# tNode-8.net
KiCad netlist of a schematic drawn in EAGLE
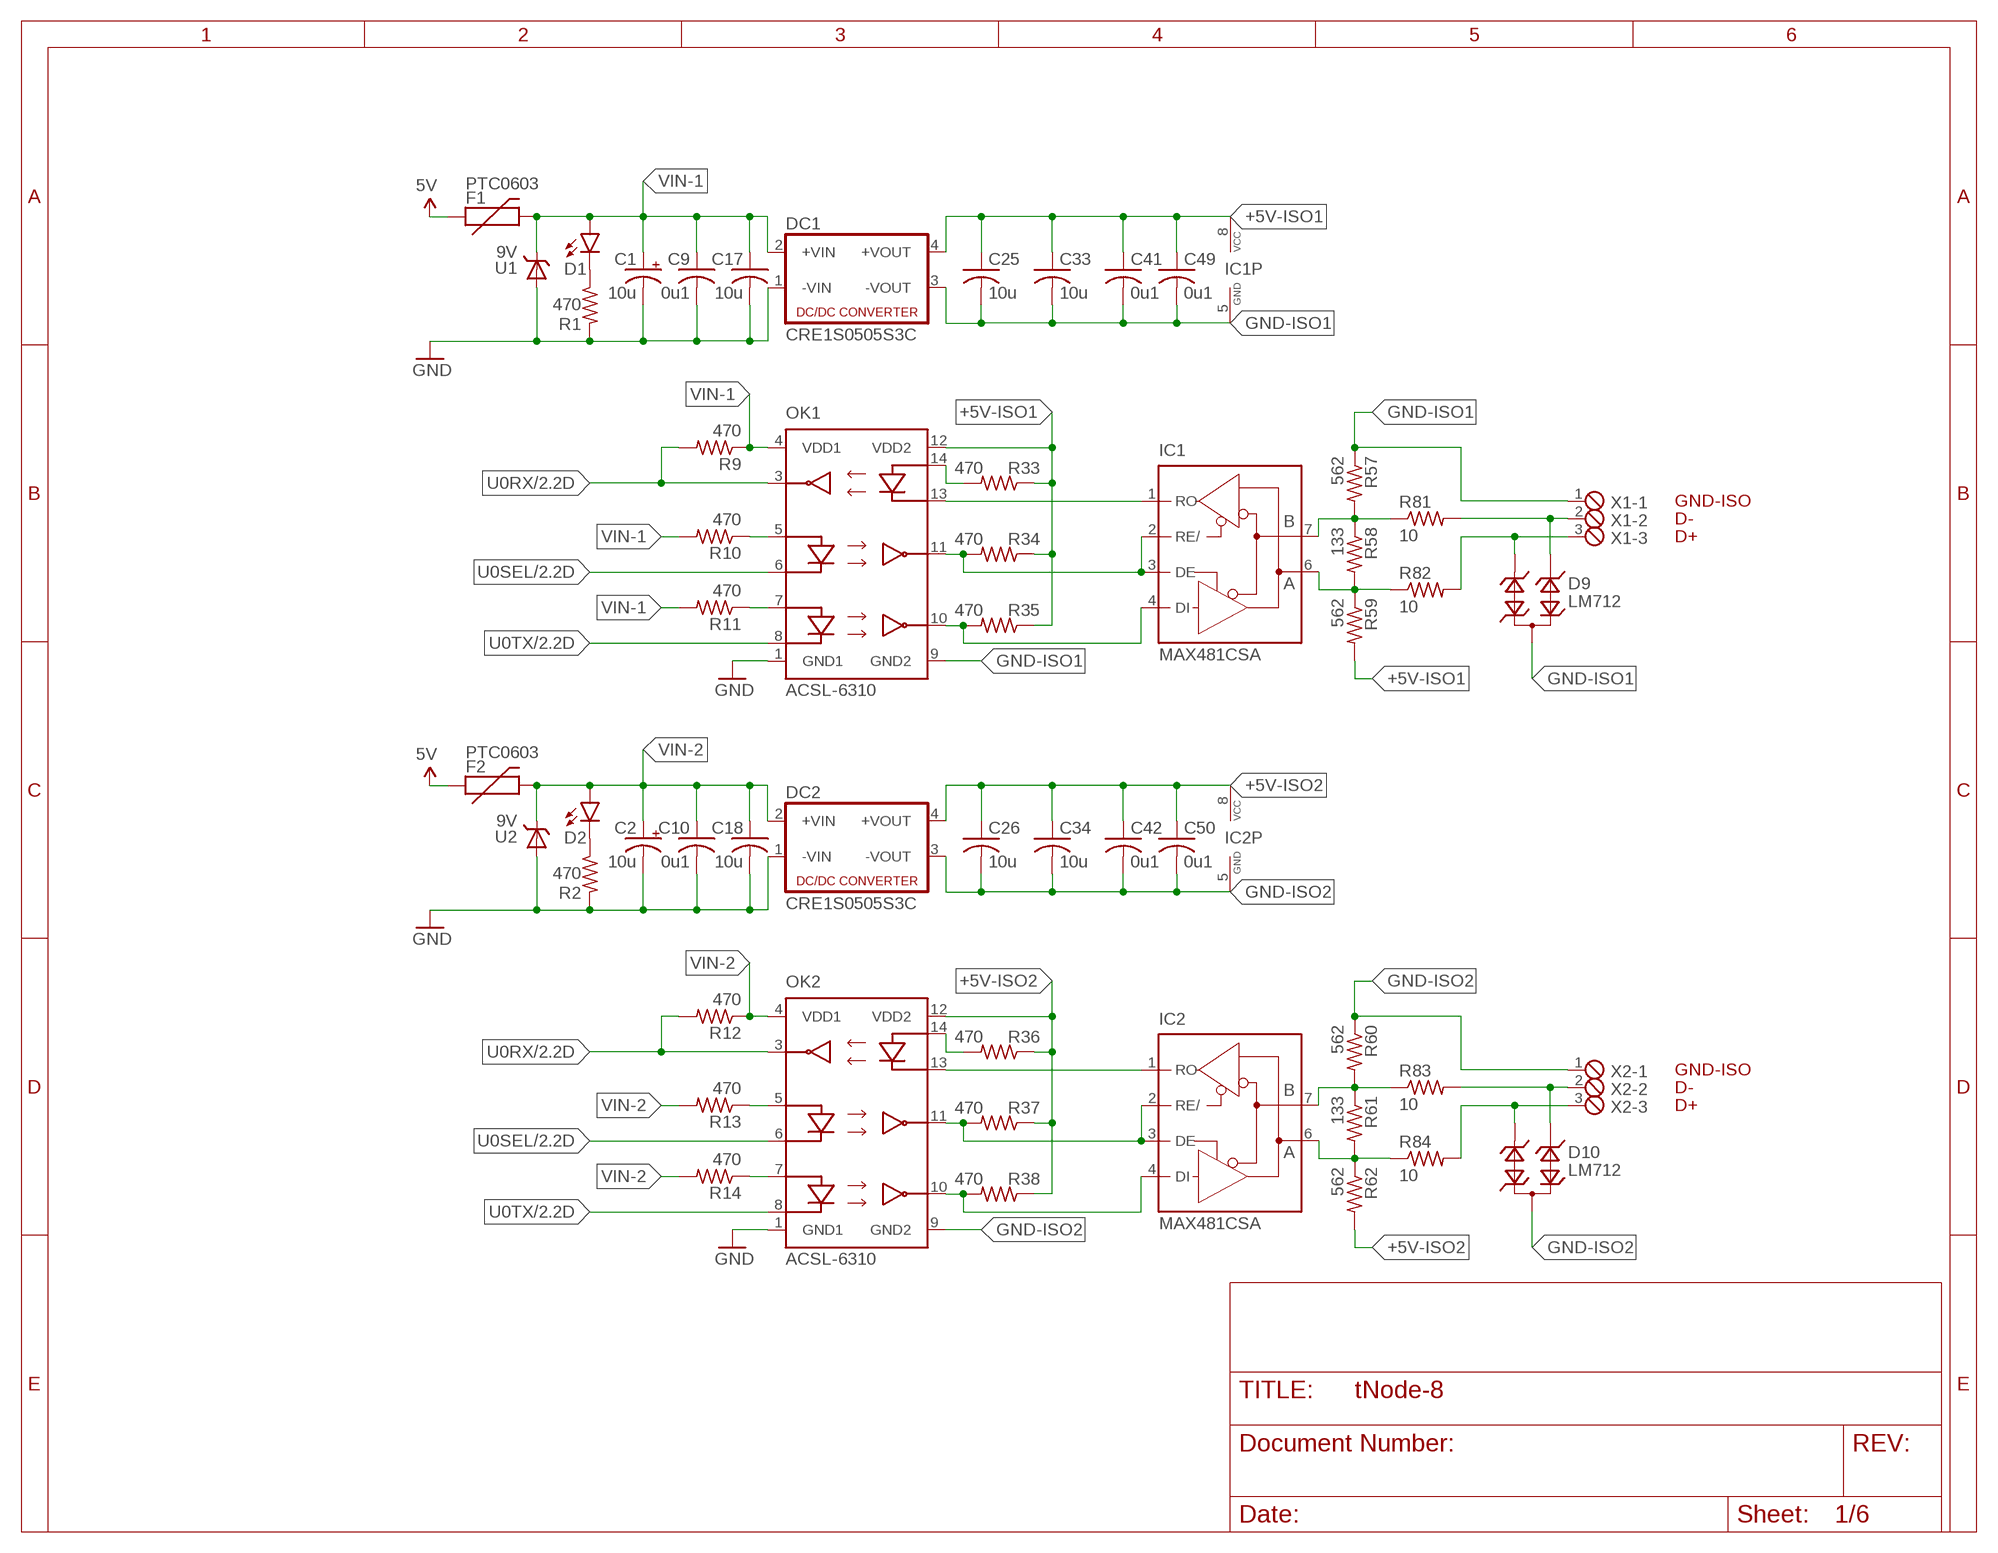
[diagram p0: schematic, sheet 1]
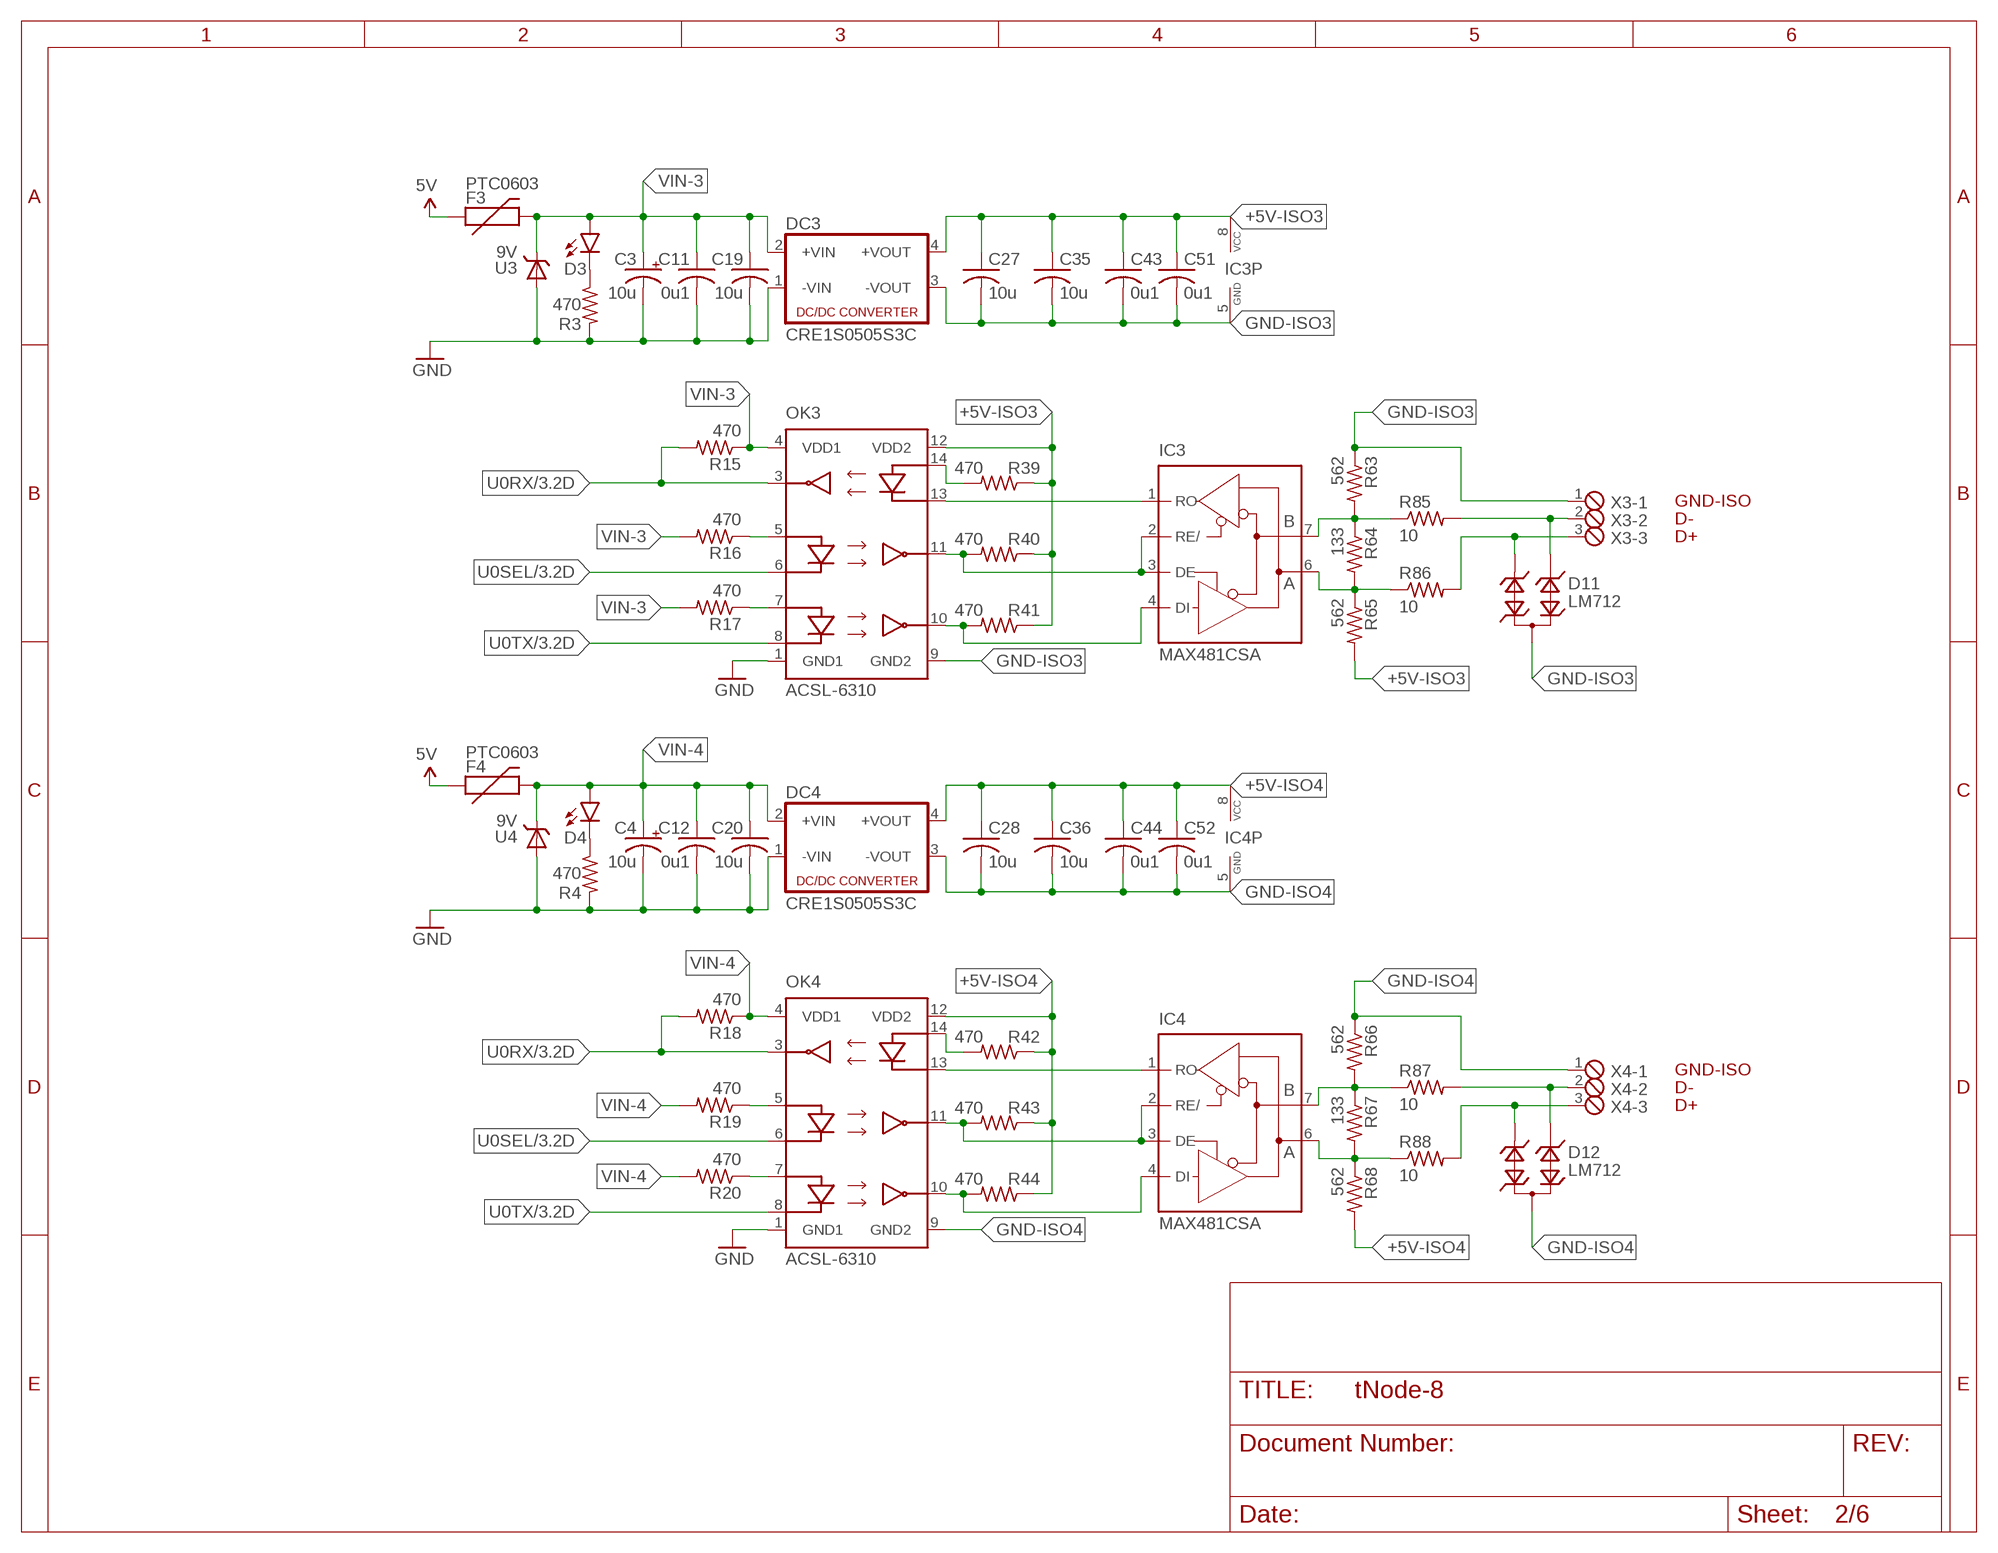
[diagram p1: schematic, sheet 2]
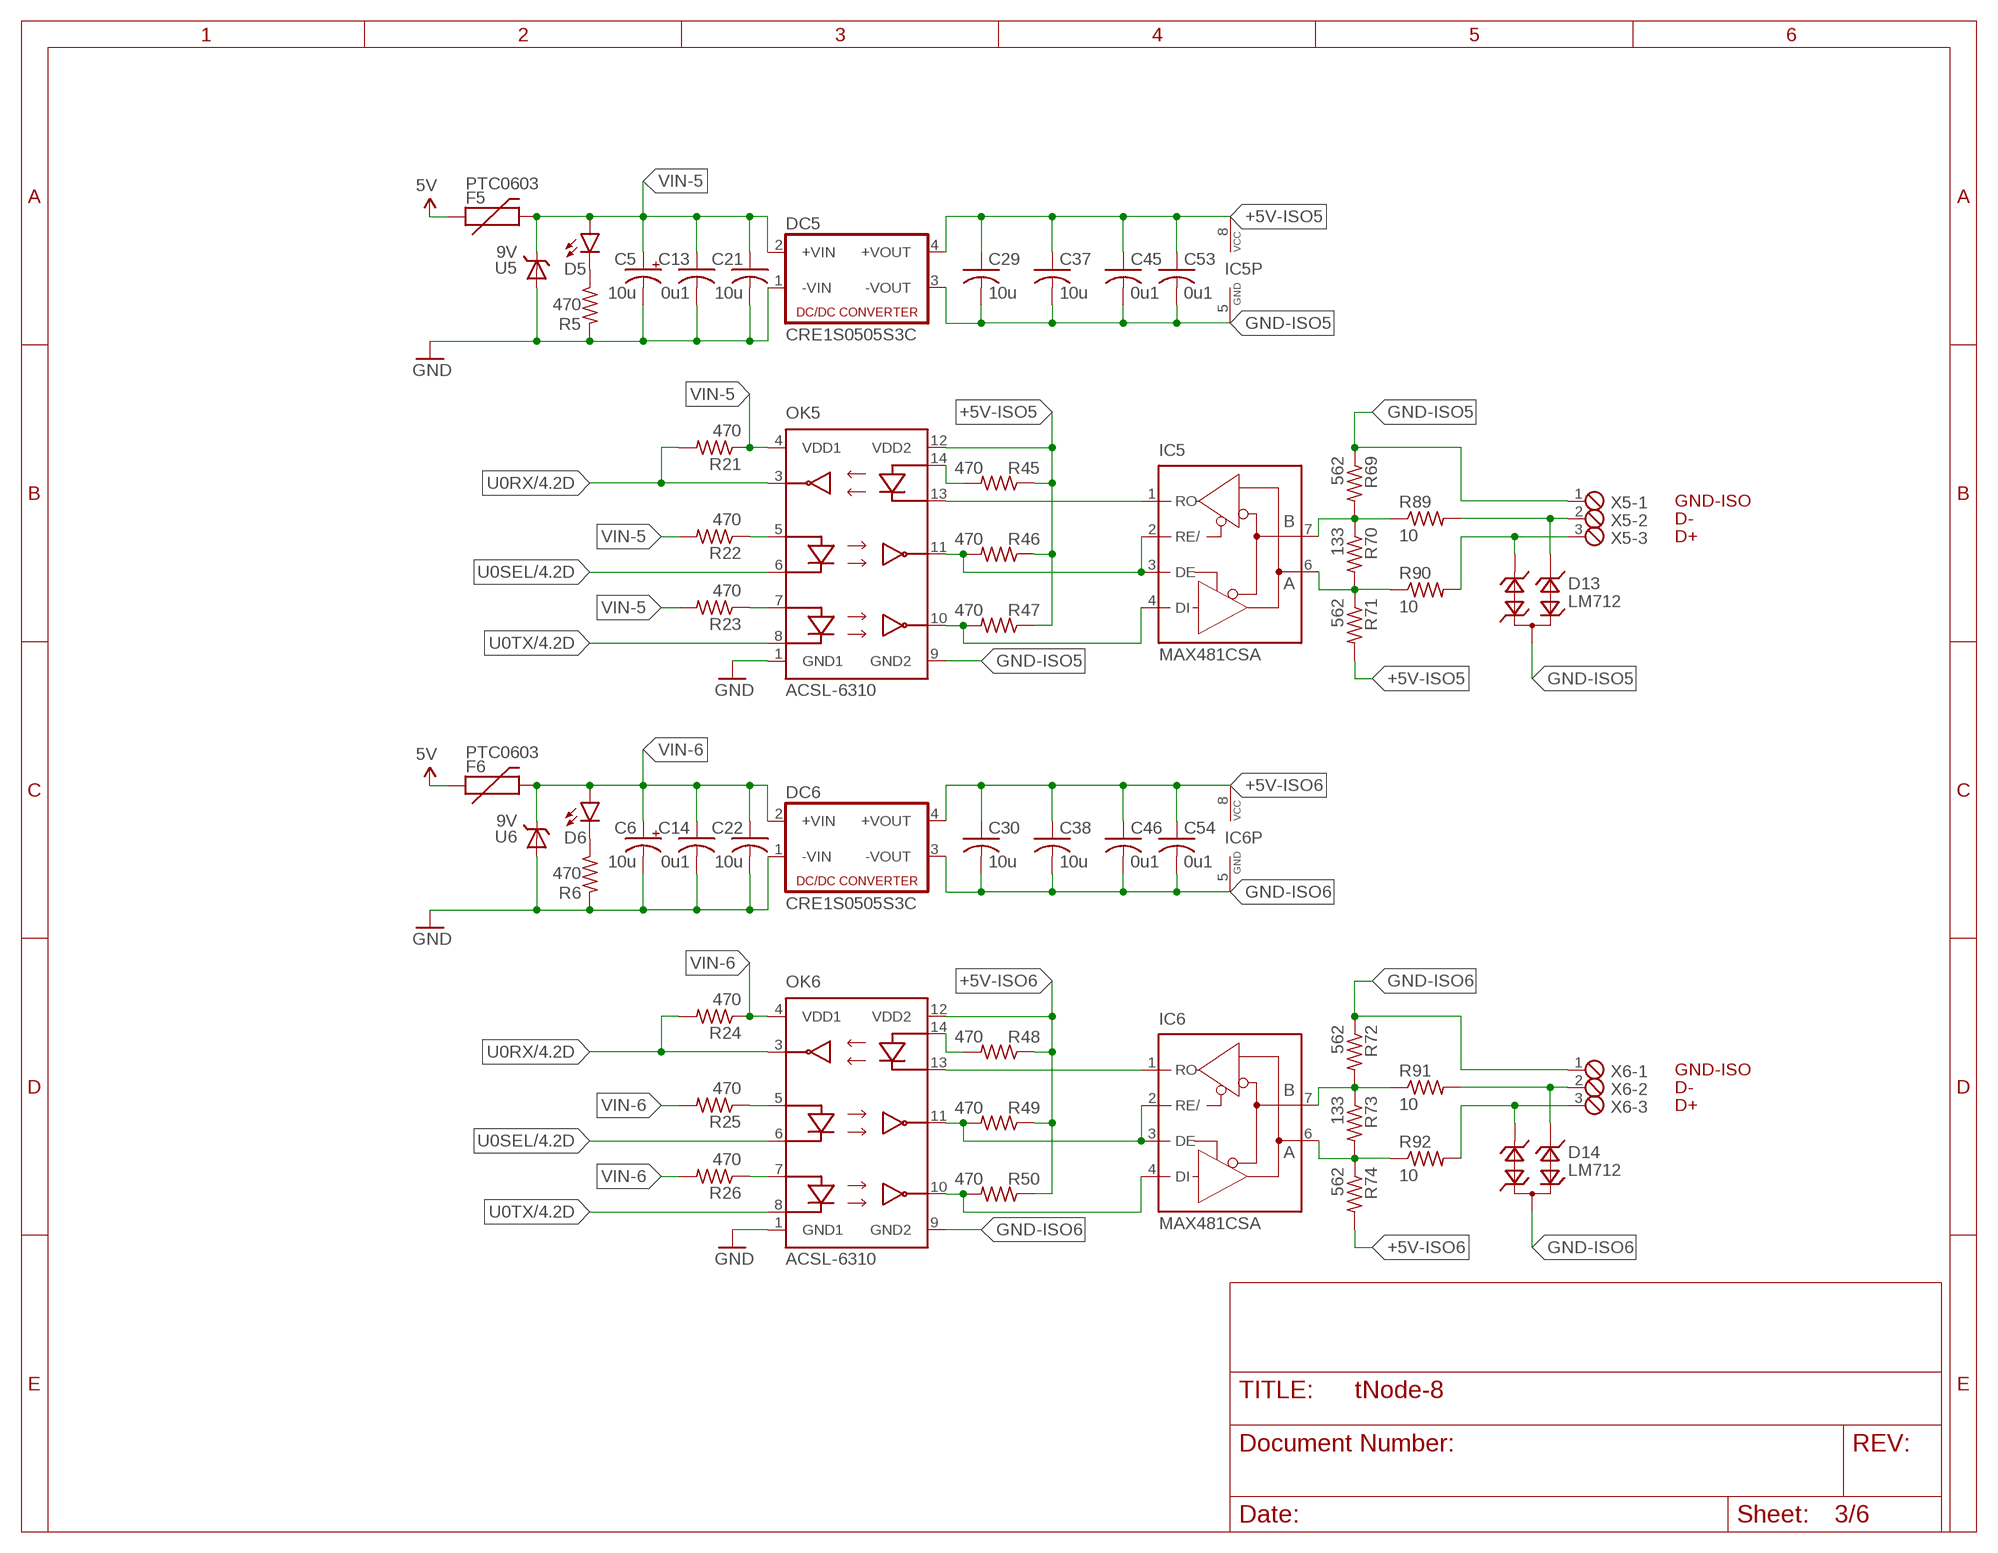
[diagram p2: schematic, sheet 3]
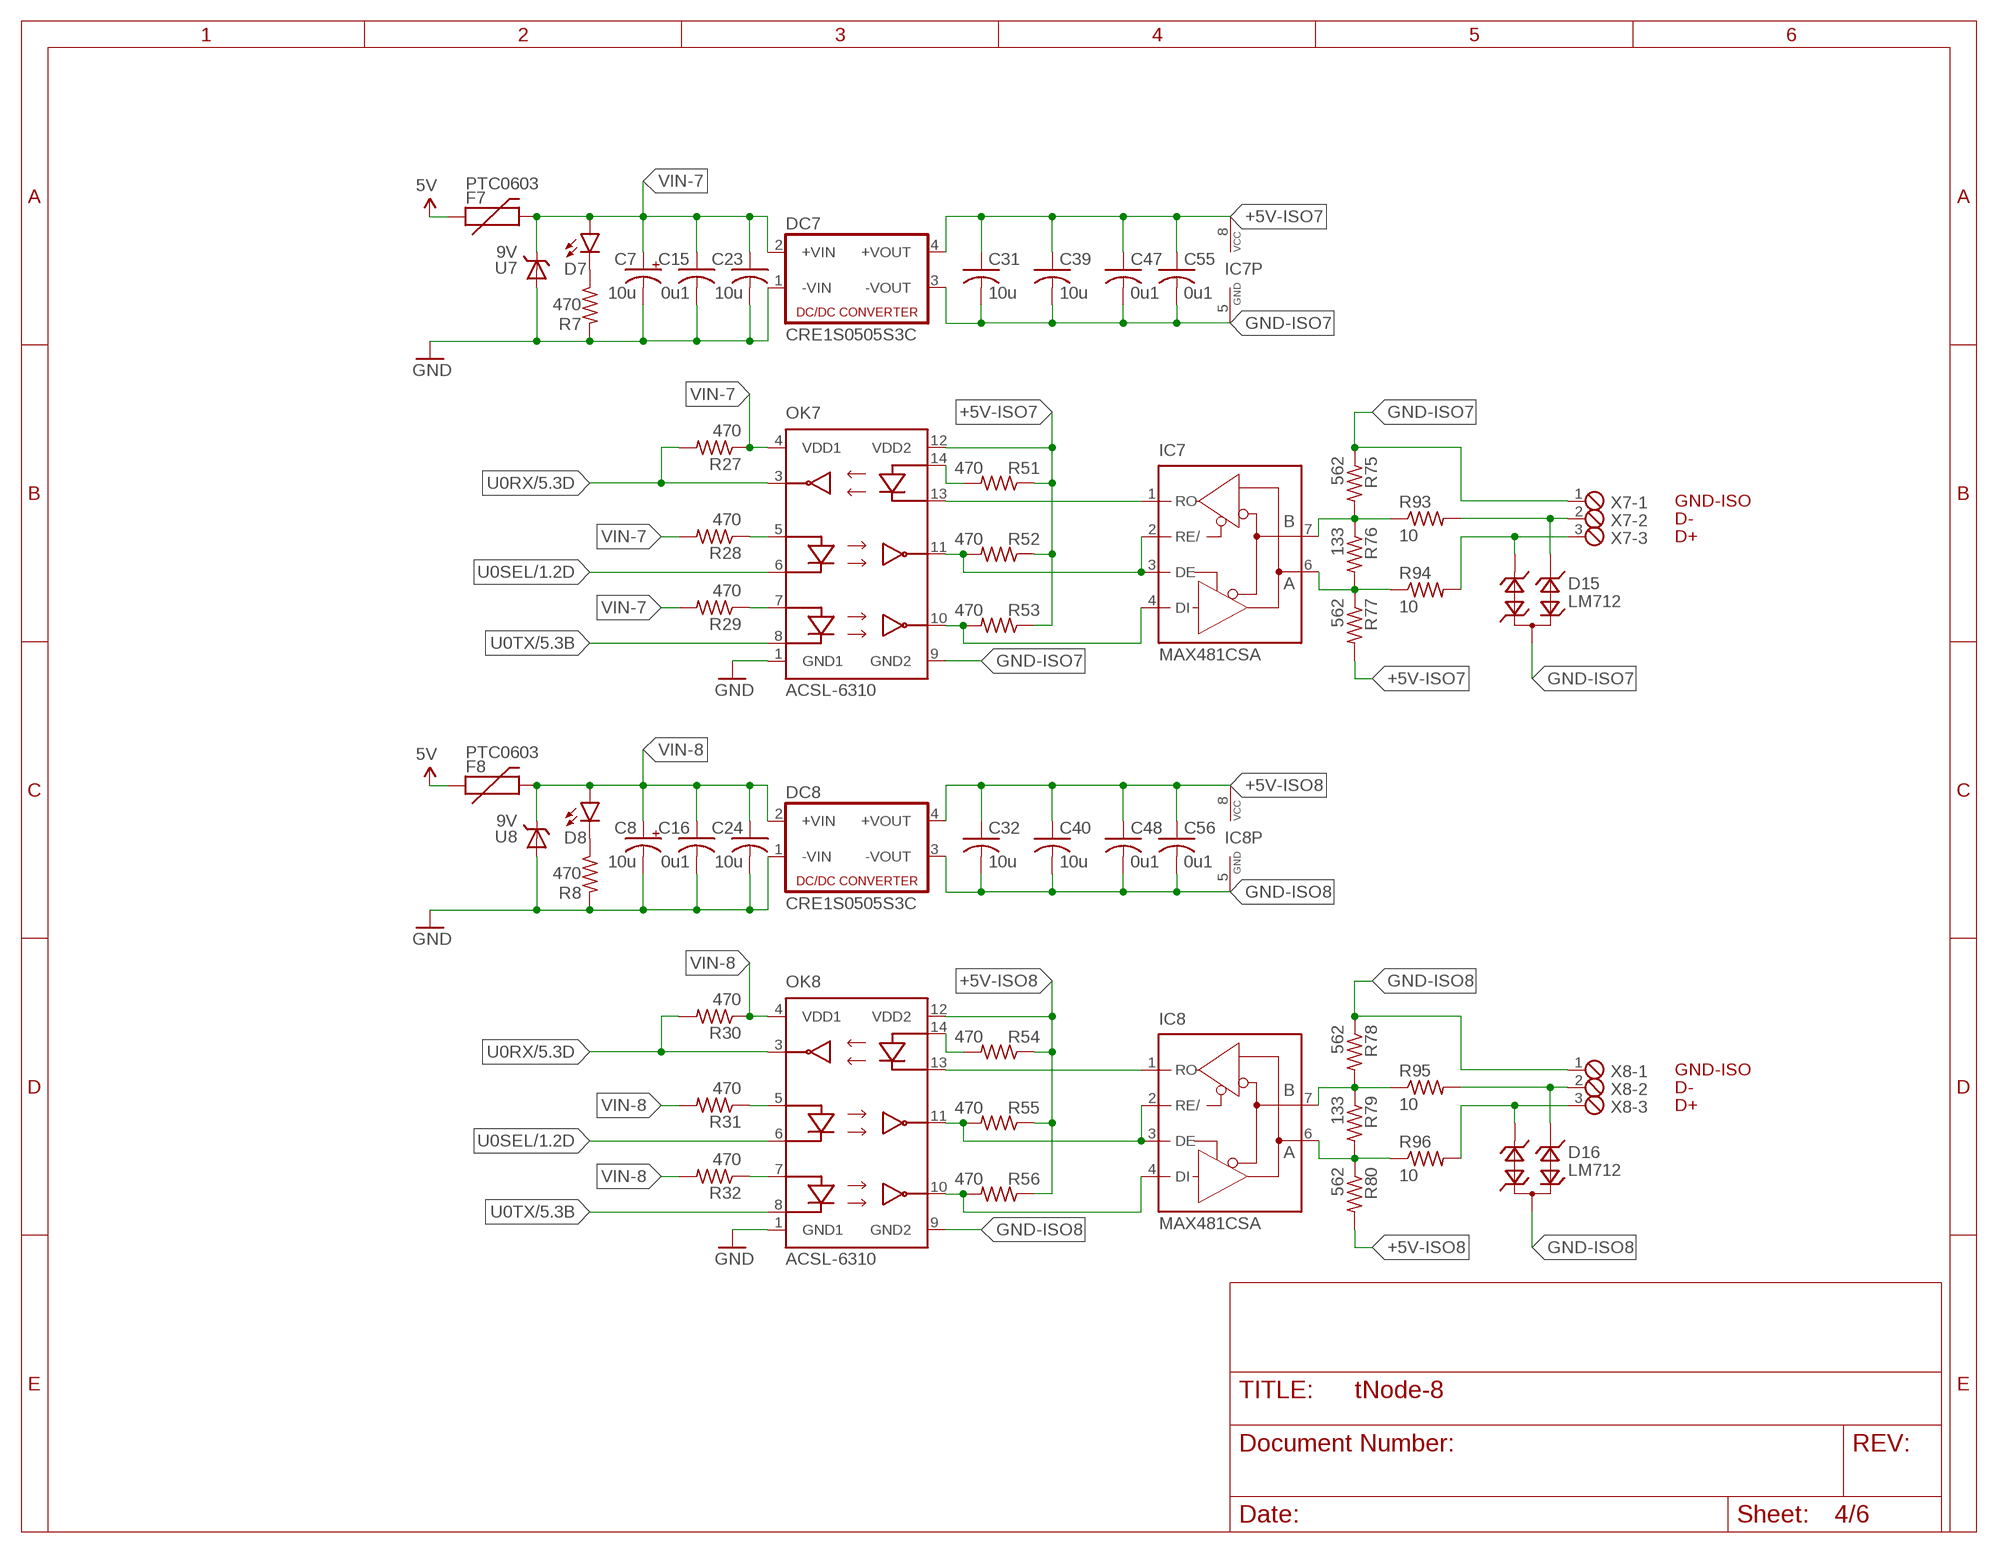
[diagram p3: schematic, sheet 4]
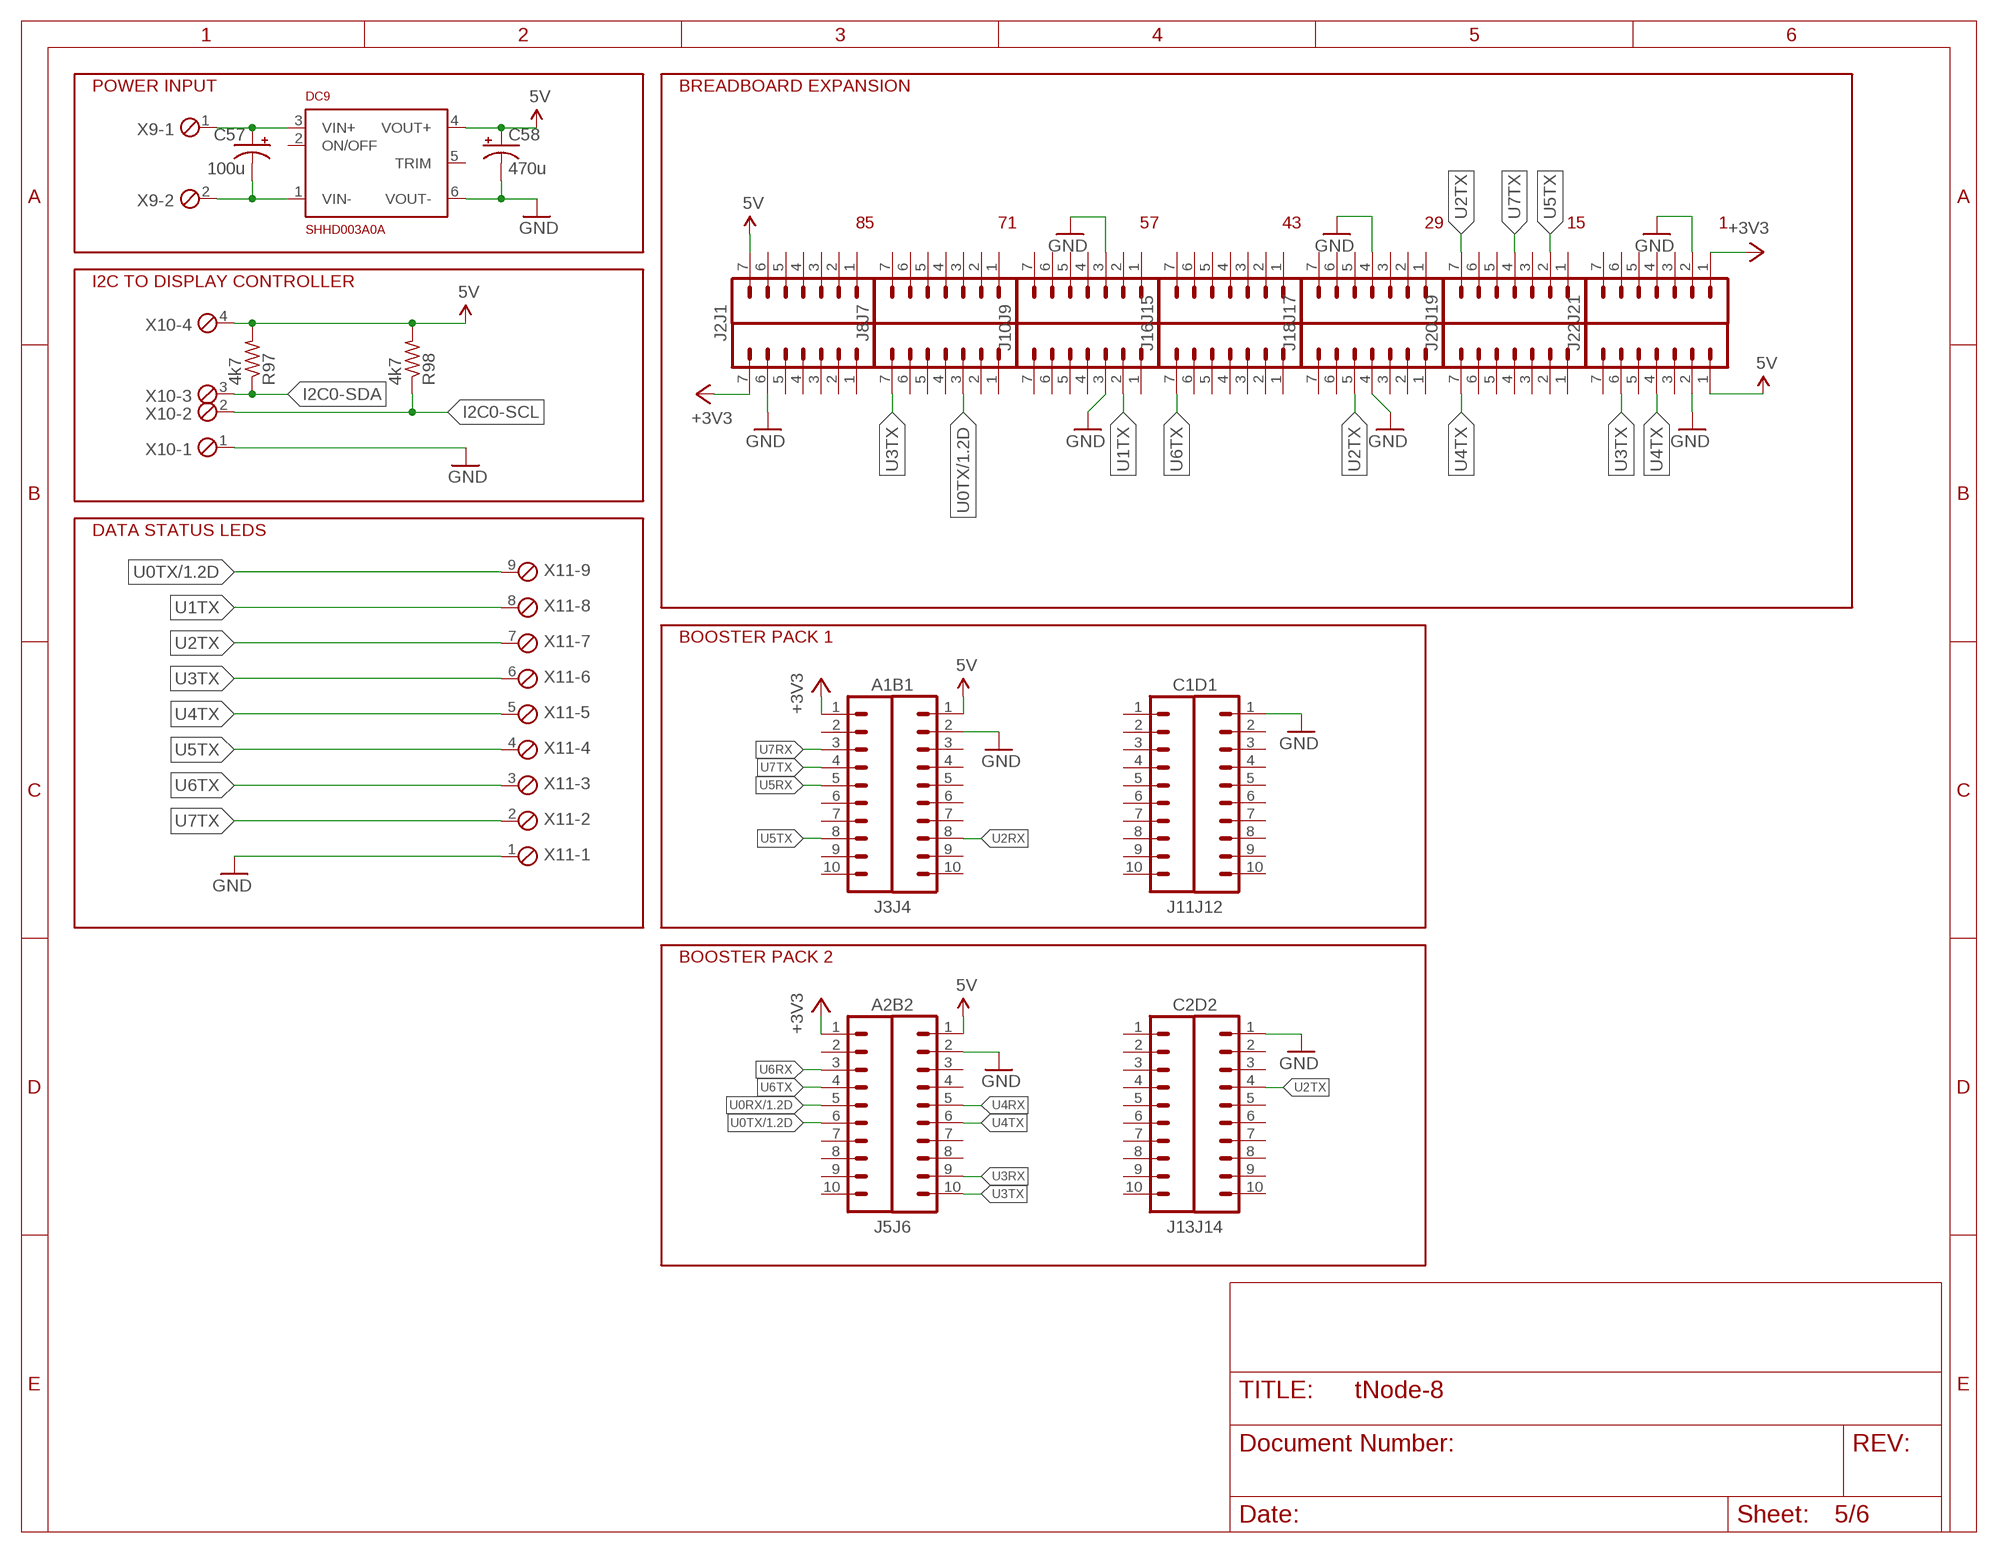
[diagram p4: schematic, sheet 5]
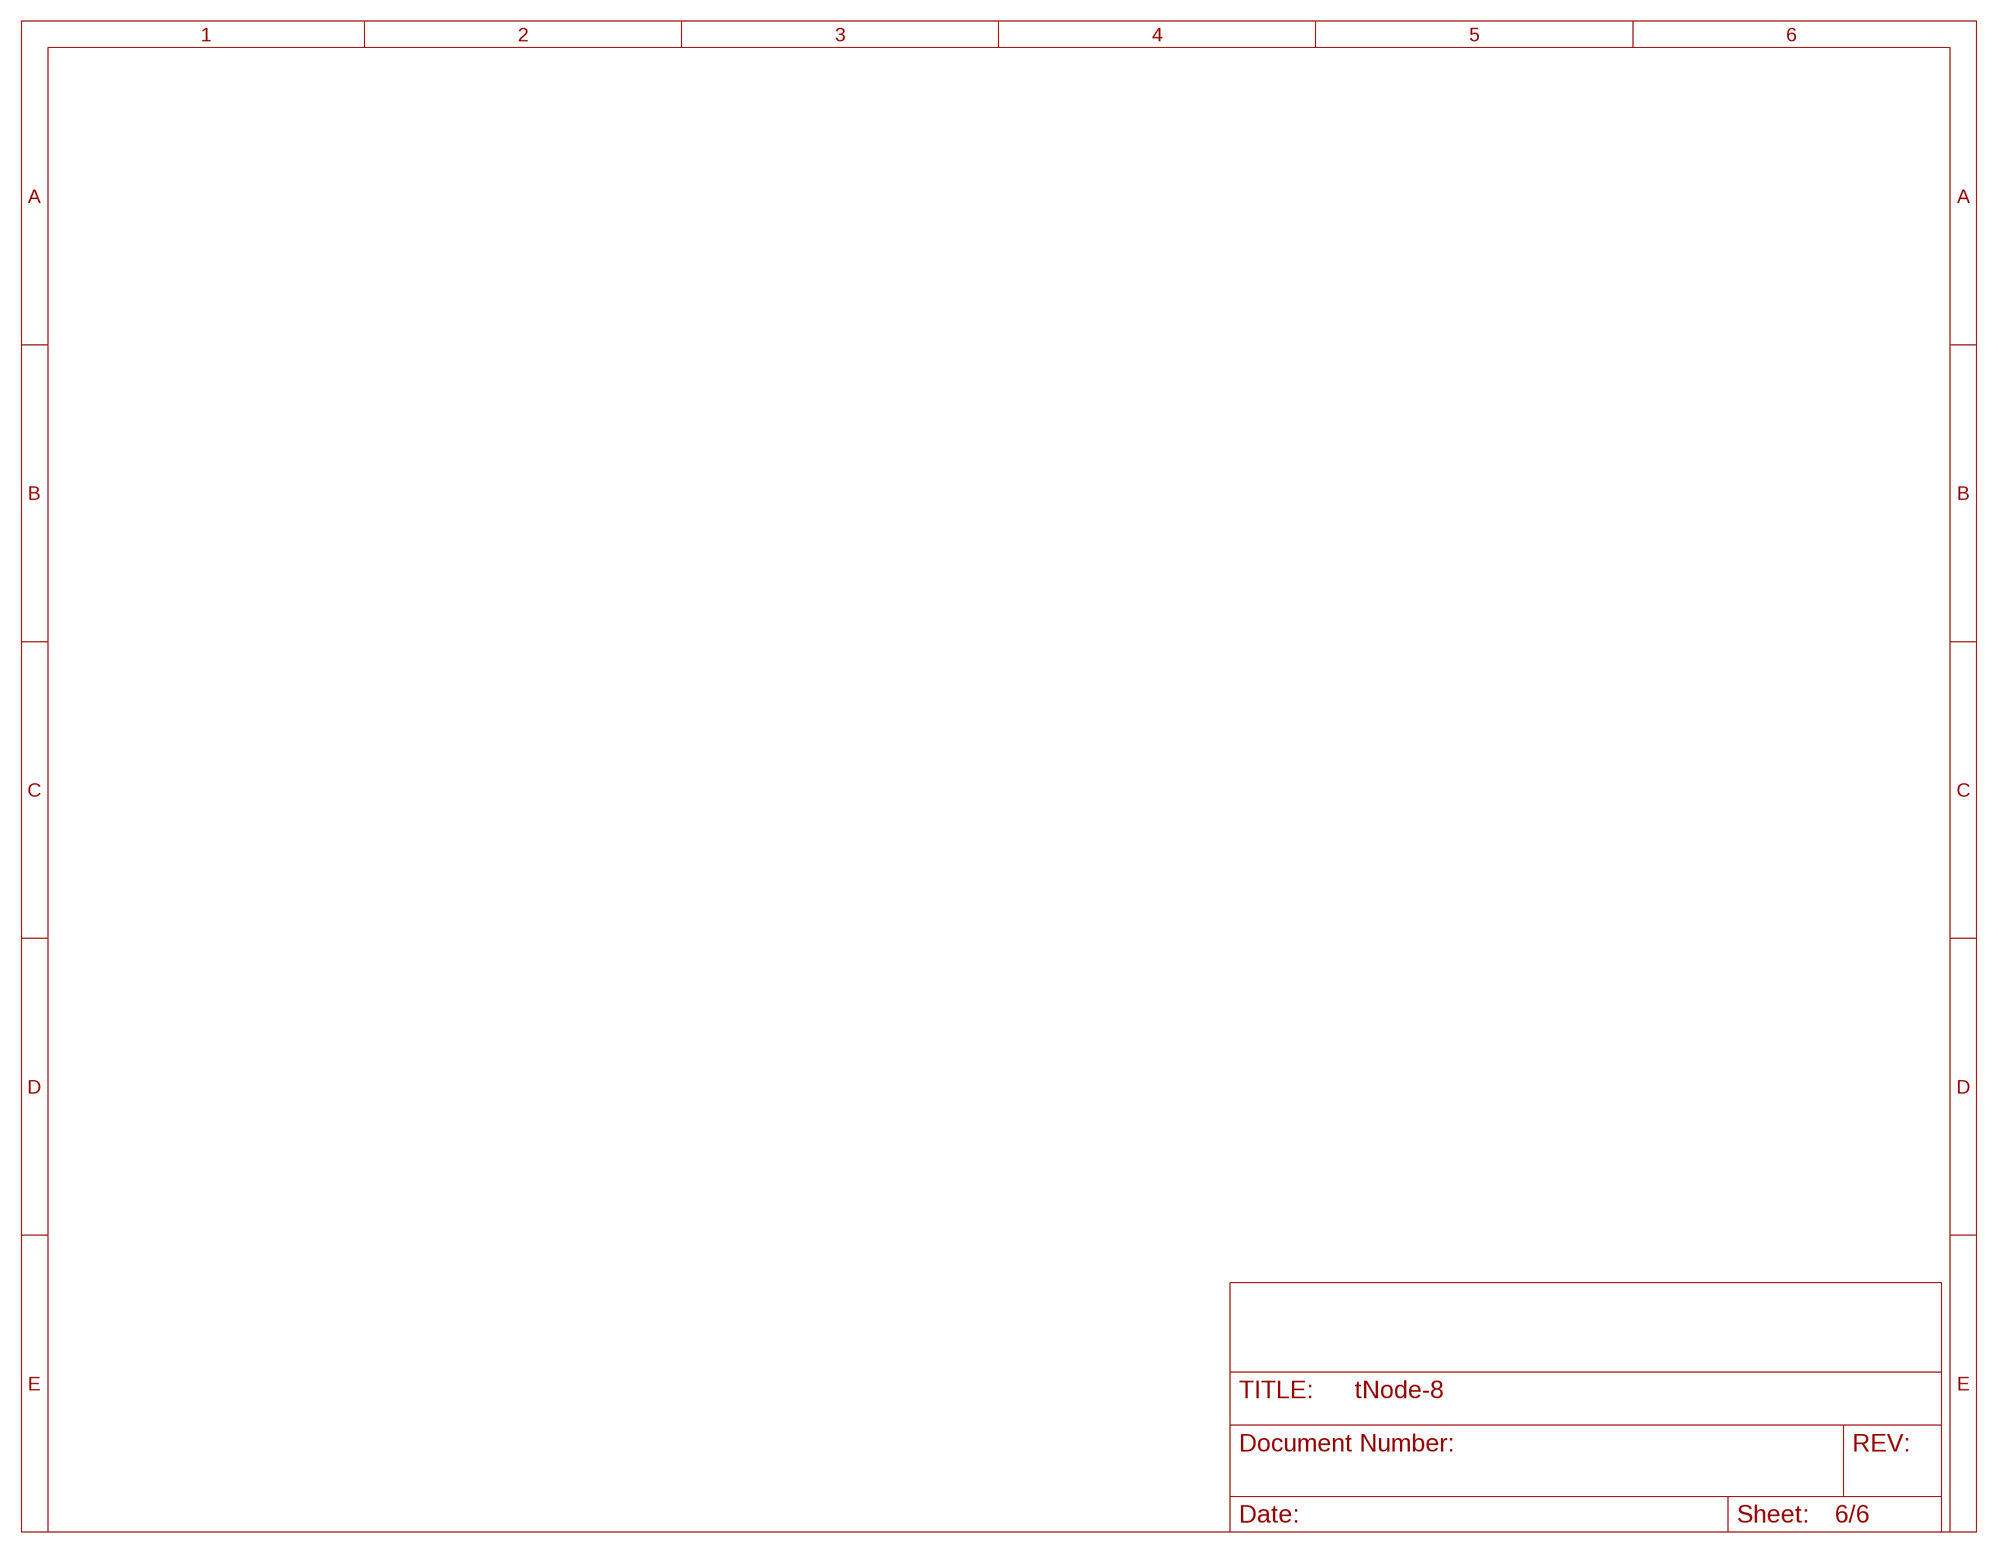
[diagram p5: schematic, sheet 6]

(export (version "E")
  (design (tool "Eeschema 10.0.6"))
  (components
    (comp (ref "C1")
      (value "10u")
      (footprint "eagle-import:E2,5-5-NOSILK")
      (libsource (lib "eagle-import") (part "CPOL-USE2.5-5-NOSILK"))
    )
    (comp (ref "C2")
      (value "10u")
      (footprint "eagle-import:E2,5-5-NOSILK")
      (libsource (lib "eagle-import") (part "CPOL-USE2.5-5-NOSILK"))
    )
    (comp (ref "C9")
      (value "0u1")
      (footprint "eagle-import:C0603K")
      (libsource (lib "eagle-import") (part "C-USC0603K"))
    )
    (comp (ref "C10")
      (value "0u1")
      (footprint "eagle-import:C0603K")
      (libsource (lib "eagle-import") (part "C-USC0603K"))
    )
    (comp (ref "C17")
      (value "10u")
      (footprint "eagle-import:C0603K")
      (libsource (lib "eagle-import") (part "C-USC0603K"))
    )
    (comp (ref "C18")
      (value "10u")
      (footprint "eagle-import:C0603K")
      (libsource (lib "eagle-import") (part "C-USC0603K"))
    )
    (comp (ref "C25")
      (value "10u")
      (footprint "eagle-import:C0603K")
      (libsource (lib "eagle-import") (part "C-USC0603K"))
    )
    (comp (ref "C26")
      (value "10u")
      (footprint "eagle-import:C0603K")
      (libsource (lib "eagle-import") (part "C-USC0603K"))
    )
    (comp (ref "C33")
      (value "10u")
      (footprint "eagle-import:C0603K")
      (libsource (lib "eagle-import") (part "C-USC0603K"))
    )
    (comp (ref "C34")
      (value "10u")
      (footprint "eagle-import:C0603K")
      (libsource (lib "eagle-import") (part "C-USC0603K"))
    )
    (comp (ref "C41")
      (value "0u1")
      (footprint "eagle-import:C0603K")
      (libsource (lib "eagle-import") (part "C-USC0603K"))
    )
    (comp (ref "C42")
      (value "0u1")
      (footprint "eagle-import:C0603K")
      (libsource (lib "eagle-import") (part "C-USC0603K"))
    )
    (comp (ref "C49")
      (value "0u1")
      (footprint "eagle-import:C0603K")
      (libsource (lib "eagle-import") (part "C-USC0603K"))
    )
    (comp (ref "C50")
      (value "0u1")
      (footprint "eagle-import:C0603K")
      (libsource (lib "eagle-import") (part "C-USC0603K"))
    )
    (comp (ref "D1")
      (value "LED0603")
      (footprint "eagle-import:LED-0603")
      (libsource (lib "eagle-import") (part "LED0603"))
    )
    (comp (ref "D2")
      (value "LED0603")
      (footprint "eagle-import:LED-0603")
      (libsource (lib "eagle-import") (part "LED0603"))
    )
    (comp (ref "D9")
      (value "LM712")
      (footprint "eagle-import:SOT23")
      (libsource (lib "eagle-import") (part "CDSOT23-SM712SOT23-STANDARD"))
    )
    (comp (ref "D10")
      (value "LM712")
      (footprint "eagle-import:SOT23")
      (libsource (lib "eagle-import") (part "CDSOT23-SM712SOT23-STANDARD"))
    )
    (comp (ref "DC1")
      (value "CRE1S0505S3C")
      (footprint "eagle-import:4SIL")
      (libsource (lib "eagle-import") (part "VA-?S0505"))
    )
    (comp (ref "DC2")
      (value "CRE1S0505S3C")
      (footprint "eagle-import:4SIL")
      (libsource (lib "eagle-import") (part "VA-?S0505"))
    )
    (comp (ref "F1")
      (value "PTC0603")
      (footprint "eagle-import:0603")
      (libsource (lib "eagle-import") (part "PTC0603"))
    )
    (comp (ref "F2")
      (value "PTC0603")
      (footprint "eagle-import:0603")
      (libsource (lib "eagle-import") (part "PTC0603"))
    )
    (comp (ref "IC1")
      (value "MAX481CSA")
      (footprint "eagle-import:SO08")
      (fields (field (name "MF") "MAXIM"))
      (libsource (lib "eagle-import") (part "MAX481CSA"))
    )
    (comp (ref "IC2")
      (value "MAX481CSA")
      (footprint "eagle-import:SO08")
      (fields (field (name "MF") "MAXIM"))
      (libsource (lib "eagle-import") (part "MAX481CSA"))
    )
    (comp (ref "OK1")
      (value "ACSL-6310")
      (footprint "eagle-import:SO-16")
      (libsource (lib "eagle-import") (part "ACSL-60"))
    )
    (comp (ref "OK2")
      (value "ACSL-6310")
      (footprint "eagle-import:SO-16")
      (libsource (lib "eagle-import") (part "ACSL-60"))
    )
    (comp (ref "R1")
      (value "470")
      (footprint "eagle-import:R0603")
      (libsource (lib "eagle-import") (part "R-US_R0603"))
    )
    (comp (ref "R2")
      (value "470")
      (footprint "eagle-import:R0603")
      (libsource (lib "eagle-import") (part "R-US_R0603"))
    )
    (comp (ref "R9")
      (value "470")
      (footprint "eagle-import:R0603")
      (libsource (lib "eagle-import") (part "R-US_R0603"))
    )
    (comp (ref "R10")
      (value "470")
      (footprint "eagle-import:R0603")
      (libsource (lib "eagle-import") (part "R-US_R0603"))
    )
    (comp (ref "R11")
      (value "470")
      (footprint "eagle-import:R0603")
      (libsource (lib "eagle-import") (part "R-US_R0603"))
    )
    (comp (ref "R12")
      (value "470")
      (footprint "eagle-import:R0603")
      (libsource (lib "eagle-import") (part "R-US_R0603"))
    )
    (comp (ref "R13")
      (value "470")
      (footprint "eagle-import:R0603")
      (libsource (lib "eagle-import") (part "R-US_R0603"))
    )
    (comp (ref "R14")
      (value "470")
      (footprint "eagle-import:R0603")
      (libsource (lib "eagle-import") (part "R-US_R0603"))
    )
    (comp (ref "R33")
      (value "470")
      (footprint "eagle-import:R0603")
      (libsource (lib "eagle-import") (part "R-US_R0603"))
    )
    (comp (ref "R34")
      (value "470")
      (footprint "eagle-import:R0603")
      (libsource (lib "eagle-import") (part "R-US_R0603"))
    )
    (comp (ref "R35")
      (value "470")
      (footprint "eagle-import:R0603")
      (libsource (lib "eagle-import") (part "R-US_R0603"))
    )
    (comp (ref "R36")
      (value "470")
      (footprint "eagle-import:R0603")
      (libsource (lib "eagle-import") (part "R-US_R0603"))
    )
    (comp (ref "R37")
      (value "470")
      (footprint "eagle-import:R0603")
      (libsource (lib "eagle-import") (part "R-US_R0603"))
    )
    (comp (ref "R38")
      (value "470")
      (footprint "eagle-import:R0603")
      (libsource (lib "eagle-import") (part "R-US_R0603"))
    )
    (comp (ref "R57")
      (value "562")
      (footprint "eagle-import:R0603")
      (libsource (lib "eagle-import") (part "R-US_R0603"))
    )
    (comp (ref "R58")
      (value "133")
      (footprint "eagle-import:R0603")
      (libsource (lib "eagle-import") (part "R-US_R0603"))
    )
    (comp (ref "R59")
      (value "562")
      (footprint "eagle-import:R0603")
      (libsource (lib "eagle-import") (part "R-US_R0603"))
    )
    (comp (ref "R60")
      (value "562")
      (footprint "eagle-import:R0603")
      (libsource (lib "eagle-import") (part "R-US_R0603"))
    )
    (comp (ref "R61")
      (value "133")
      (footprint "eagle-import:R0603")
      (libsource (lib "eagle-import") (part "R-US_R0603"))
    )
    (comp (ref "R62")
      (value "562")
      (footprint "eagle-import:R0603")
      (libsource (lib "eagle-import") (part "R-US_R0603"))
    )
    (comp (ref "R81")
      (value "10")
      (footprint "eagle-import:R0603")
      (libsource (lib "eagle-import") (part "R-US_R0603"))
    )
    (comp (ref "R82")
      (value "10")
      (footprint "eagle-import:R0603")
      (libsource (lib "eagle-import") (part "R-US_R0603"))
    )
    (comp (ref "R83")
      (value "10")
      (footprint "eagle-import:R0603")
      (libsource (lib "eagle-import") (part "R-US_R0603"))
    )
    (comp (ref "R84")
      (value "10")
      (footprint "eagle-import:R0603")
      (libsource (lib "eagle-import") (part "R-US_R0603"))
    )
    (comp (ref "U1")
      (value "9V")
      (footprint "eagle-import:SOD323-NOSILK")
      (libsource (lib "eagle-import") (part "TVS-DIODESOD323-NOSILK"))
    )
    (comp (ref "U2")
      (value "9V")
      (footprint "eagle-import:SOD323-NOSILK")
      (libsource (lib "eagle-import") (part "TVS-DIODESOD323-NOSILK"))
    )
    (comp (ref "X1")
      (value "MPT3")
      (footprint "eagle-import:3POL254")
      (libsource (lib "eagle-import") (part "MPT3"))
    )
    (comp (ref "X2")
      (value "MPT3")
      (footprint "eagle-import:3POL254")
      (libsource (lib "eagle-import") (part "MPT3"))
    )
    (comp (ref "C7")
      (value "10u")
      (footprint "eagle-import:E2,5-5-NOSILK")
      (libsource (lib "eagle-import") (part "CPOL-USE2.5-5-NOSILK"))
    )
    (comp (ref "C8")
      (value "10u")
      (footprint "eagle-import:E2,5-5-NOSILK")
      (libsource (lib "eagle-import") (part "CPOL-USE2.5-5-NOSILK"))
    )
    (comp (ref "C15")
      (value "0u1")
      (footprint "eagle-import:C0603K")
      (libsource (lib "eagle-import") (part "C-USC0603K"))
    )
    (comp (ref "C16")
      (value "0u1")
      (footprint "eagle-import:C0603K")
      (libsource (lib "eagle-import") (part "C-USC0603K"))
    )
    (comp (ref "C23")
      (value "10u")
      (footprint "eagle-import:C0603K")
      (libsource (lib "eagle-import") (part "C-USC0603K"))
    )
    (comp (ref "C24")
      (value "10u")
      (footprint "eagle-import:C0603K")
      (libsource (lib "eagle-import") (part "C-USC0603K"))
    )
    (comp (ref "C31")
      (value "10u")
      (footprint "eagle-import:C0603K")
      (libsource (lib "eagle-import") (part "C-USC0603K"))
    )
    (comp (ref "C32")
      (value "10u")
      (footprint "eagle-import:C0603K")
      (libsource (lib "eagle-import") (part "C-USC0603K"))
    )
    (comp (ref "C39")
      (value "10u")
      (footprint "eagle-import:C0603K")
      (libsource (lib "eagle-import") (part "C-USC0603K"))
    )
    (comp (ref "C40")
      (value "10u")
      (footprint "eagle-import:C0603K")
      (libsource (lib "eagle-import") (part "C-USC0603K"))
    )
    (comp (ref "C47")
      (value "0u1")
      (footprint "eagle-import:C0603K")
      (libsource (lib "eagle-import") (part "C-USC0603K"))
    )
    (comp (ref "C48")
      (value "0u1")
      (footprint "eagle-import:C0603K")
      (libsource (lib "eagle-import") (part "C-USC0603K"))
    )
    (comp (ref "C55")
      (value "0u1")
      (footprint "eagle-import:C0603K")
      (libsource (lib "eagle-import") (part "C-USC0603K"))
    )
    (comp (ref "C56")
      (value "0u1")
      (footprint "eagle-import:C0603K")
      (libsource (lib "eagle-import") (part "C-USC0603K"))
    )
    (comp (ref "D7")
      (value "LED0603")
      (footprint "eagle-import:LED-0603")
      (libsource (lib "eagle-import") (part "LED0603"))
    )
    (comp (ref "D8")
      (value "LED0603")
      (footprint "eagle-import:LED-0603")
      (libsource (lib "eagle-import") (part "LED0603"))
    )
    (comp (ref "D15")
      (value "LM712")
      (footprint "eagle-import:SOT23")
      (libsource (lib "eagle-import") (part "CDSOT23-SM712SOT23-STANDARD"))
    )
    (comp (ref "D16")
      (value "LM712")
      (footprint "eagle-import:SOT23")
      (libsource (lib "eagle-import") (part "CDSOT23-SM712SOT23-STANDARD"))
    )
    (comp (ref "DC7")
      (value "CRE1S0505S3C")
      (footprint "eagle-import:4SIL")
      (libsource (lib "eagle-import") (part "VA-?S0505"))
    )
    (comp (ref "DC8")
      (value "CRE1S0505S3C")
      (footprint "eagle-import:4SIL")
      (libsource (lib "eagle-import") (part "VA-?S0505"))
    )
    (comp (ref "F7")
      (value "PTC0603")
      (footprint "eagle-import:0603")
      (libsource (lib "eagle-import") (part "PTC0603"))
    )
    (comp (ref "F8")
      (value "PTC0603")
      (footprint "eagle-import:0603")
      (libsource (lib "eagle-import") (part "PTC0603"))
    )
    (comp (ref "IC7")
      (value "MAX481CSA")
      (footprint "eagle-import:SO08")
      (fields (field (name "MF") "MAXIM"))
      (libsource (lib "eagle-import") (part "MAX481CSA"))
    )
    (comp (ref "IC8")
      (value "MAX481CSA")
      (footprint "eagle-import:SO08")
      (fields (field (name "MF") "MAXIM"))
      (libsource (lib "eagle-import") (part "MAX481CSA"))
    )
    (comp (ref "OK7")
      (value "ACSL-6310")
      (footprint "eagle-import:SO-16")
      (libsource (lib "eagle-import") (part "ACSL-60"))
    )
    (comp (ref "OK8")
      (value "ACSL-6310")
      (footprint "eagle-import:SO-16")
      (libsource (lib "eagle-import") (part "ACSL-60"))
    )
    (comp (ref "R7")
      (value "470")
      (footprint "eagle-import:R0603")
      (libsource (lib "eagle-import") (part "R-US_R0603"))
    )
    (comp (ref "R8")
      (value "470")
      (footprint "eagle-import:R0603")
      (libsource (lib "eagle-import") (part "R-US_R0603"))
    )
    (comp (ref "R27")
      (value "470")
      (footprint "eagle-import:R0603")
      (libsource (lib "eagle-import") (part "R-US_R0603"))
    )
    (comp (ref "R28")
      (value "470")
      (footprint "eagle-import:R0603")
      (libsource (lib "eagle-import") (part "R-US_R0603"))
    )
    (comp (ref "R29")
      (value "470")
      (footprint "eagle-import:R0603")
      (libsource (lib "eagle-import") (part "R-US_R0603"))
    )
    (comp (ref "R30")
      (value "470")
      (footprint "eagle-import:R0603")
      (libsource (lib "eagle-import") (part "R-US_R0603"))
    )
    (comp (ref "R31")
      (value "470")
      (footprint "eagle-import:R0603")
      (libsource (lib "eagle-import") (part "R-US_R0603"))
    )
    (comp (ref "R32")
      (value "470")
      (footprint "eagle-import:R0603")
      (libsource (lib "eagle-import") (part "R-US_R0603"))
    )
    (comp (ref "R51")
      (value "470")
      (footprint "eagle-import:R0603")
      (libsource (lib "eagle-import") (part "R-US_R0603"))
    )
    (comp (ref "R52")
      (value "470")
      (footprint "eagle-import:R0603")
      (libsource (lib "eagle-import") (part "R-US_R0603"))
    )
    (comp (ref "R53")
      (value "470")
      (footprint "eagle-import:R0603")
      (libsource (lib "eagle-import") (part "R-US_R0603"))
    )
    (comp (ref "R54")
      (value "470")
      (footprint "eagle-import:R0603")
      (libsource (lib "eagle-import") (part "R-US_R0603"))
    )
    (comp (ref "R55")
      (value "470")
      (footprint "eagle-import:R0603")
      (libsource (lib "eagle-import") (part "R-US_R0603"))
    )
    (comp (ref "R56")
      (value "470")
      (footprint "eagle-import:R0603")
      (libsource (lib "eagle-import") (part "R-US_R0603"))
    )
    (comp (ref "R75")
      (value "562")
      (footprint "eagle-import:R0603")
      (libsource (lib "eagle-import") (part "R-US_R0603"))
    )
    (comp (ref "R76")
      (value "133")
      (footprint "eagle-import:R0603")
      (libsource (lib "eagle-import") (part "R-US_R0603"))
    )
    (comp (ref "R77")
      (value "562")
      (footprint "eagle-import:R0603")
      (libsource (lib "eagle-import") (part "R-US_R0603"))
    )
    (comp (ref "R78")
      (value "562")
      (footprint "eagle-import:R0603")
      (libsource (lib "eagle-import") (part "R-US_R0603"))
    )
    (comp (ref "R79")
      (value "133")
      (footprint "eagle-import:R0603")
      (libsource (lib "eagle-import") (part "R-US_R0603"))
    )
    (comp (ref "R80")
      (value "562")
      (footprint "eagle-import:R0603")
      (libsource (lib "eagle-import") (part "R-US_R0603"))
    )
    (comp (ref "R93")
      (value "10")
      (footprint "eagle-import:R0603")
      (libsource (lib "eagle-import") (part "R-US_R0603"))
    )
    (comp (ref "R94")
      (value "10")
      (footprint "eagle-import:R0603")
      (libsource (lib "eagle-import") (part "R-US_R0603"))
    )
    (comp (ref "R95")
      (value "10")
      (footprint "eagle-import:R0603")
      (libsource (lib "eagle-import") (part "R-US_R0603"))
    )
    (comp (ref "R96")
      (value "10")
      (footprint "eagle-import:R0603")
      (libsource (lib "eagle-import") (part "R-US_R0603"))
    )
    (comp (ref "U7")
      (value "9V")
      (footprint "eagle-import:SOD323-NOSILK")
      (libsource (lib "eagle-import") (part "TVS-DIODESOD323-NOSILK"))
    )
    (comp (ref "U8")
      (value "9V")
      (footprint "eagle-import:SOD323-NOSILK")
      (libsource (lib "eagle-import") (part "TVS-DIODESOD323-NOSILK"))
    )
    (comp (ref "X7")
      (value "MPT3")
      (footprint "eagle-import:3POL254")
      (libsource (lib "eagle-import") (part "MPT3"))
    )
    (comp (ref "X8")
      (value "MPT3")
      (footprint "eagle-import:3POL254")
      (libsource (lib "eagle-import") (part "MPT3"))
    )
    (comp (ref "C5")
      (value "10u")
      (footprint "eagle-import:E2,5-5-NOSILK")
      (libsource (lib "eagle-import") (part "CPOL-USE2.5-5-NOSILK"))
    )
    (comp (ref "C6")
      (value "10u")
      (footprint "eagle-import:E2,5-5-NOSILK")
      (libsource (lib "eagle-import") (part "CPOL-USE2.5-5-NOSILK"))
    )
    (comp (ref "C13")
      (value "0u1")
      (footprint "eagle-import:C0603K")
      (libsource (lib "eagle-import") (part "C-USC0603K"))
    )
    (comp (ref "C14")
      (value "0u1")
      (footprint "eagle-import:C0603K")
      (libsource (lib "eagle-import") (part "C-USC0603K"))
    )
    (comp (ref "C21")
      (value "10u")
      (footprint "eagle-import:C0603K")
      (libsource (lib "eagle-import") (part "C-USC0603K"))
    )
    (comp (ref "C22")
      (value "10u")
      (footprint "eagle-import:C0603K")
      (libsource (lib "eagle-import") (part "C-USC0603K"))
    )
    (comp (ref "C29")
      (value "10u")
      (footprint "eagle-import:C0603K")
      (libsource (lib "eagle-import") (part "C-USC0603K"))
    )
    (comp (ref "C30")
      (value "10u")
      (footprint "eagle-import:C0603K")
      (libsource (lib "eagle-import") (part "C-USC0603K"))
    )
    (comp (ref "C37")
      (value "10u")
      (footprint "eagle-import:C0603K")
      (libsource (lib "eagle-import") (part "C-USC0603K"))
    )
    (comp (ref "C38")
      (value "10u")
      (footprint "eagle-import:C0603K")
      (libsource (lib "eagle-import") (part "C-USC0603K"))
    )
    (comp (ref "C45")
      (value "0u1")
      (footprint "eagle-import:C0603K")
      (libsource (lib "eagle-import") (part "C-USC0603K"))
    )
    (comp (ref "C46")
      (value "0u1")
      (footprint "eagle-import:C0603K")
      (libsource (lib "eagle-import") (part "C-USC0603K"))
    )
    (comp (ref "C53")
      (value "0u1")
      (footprint "eagle-import:C0603K")
      (libsource (lib "eagle-import") (part "C-USC0603K"))
    )
    (comp (ref "C54")
      (value "0u1")
      (footprint "eagle-import:C0603K")
      (libsource (lib "eagle-import") (part "C-USC0603K"))
    )
    (comp (ref "D5")
      (value "LED0603")
      (footprint "eagle-import:LED-0603")
      (libsource (lib "eagle-import") (part "LED0603"))
    )
    (comp (ref "D6")
      (value "LED0603")
      (footprint "eagle-import:LED-0603")
      (libsource (lib "eagle-import") (part "LED0603"))
    )
    (comp (ref "D13")
      (value "LM712")
      (footprint "eagle-import:SOT23")
      (libsource (lib "eagle-import") (part "CDSOT23-SM712SOT23-STANDARD"))
    )
    (comp (ref "D14")
      (value "LM712")
      (footprint "eagle-import:SOT23")
      (libsource (lib "eagle-import") (part "CDSOT23-SM712SOT23-STANDARD"))
    )
    (comp (ref "DC5")
      (value "CRE1S0505S3C")
      (footprint "eagle-import:4SIL")
      (libsource (lib "eagle-import") (part "VA-?S0505"))
    )
    (comp (ref "DC6")
      (value "CRE1S0505S3C")
      (footprint "eagle-import:4SIL")
      (libsource (lib "eagle-import") (part "VA-?S0505"))
    )
    (comp (ref "F5")
      (value "PTC0603")
      (footprint "eagle-import:0603")
      (libsource (lib "eagle-import") (part "PTC0603"))
    )
    (comp (ref "F6")
      (value "PTC0603")
      (footprint "eagle-import:0603")
      (libsource (lib "eagle-import") (part "PTC0603"))
    )
    (comp (ref "IC5")
      (value "MAX481CSA")
      (footprint "eagle-import:SO08")
      (fields (field (name "MF") "MAXIM"))
      (libsource (lib "eagle-import") (part "MAX481CSA"))
    )
    (comp (ref "IC6")
      (value "MAX481CSA")
      (footprint "eagle-import:SO08")
      (fields (field (name "MF") "MAXIM"))
      (libsource (lib "eagle-import") (part "MAX481CSA"))
    )
    (comp (ref "OK5")
      (value "ACSL-6310")
      (footprint "eagle-import:SO-16")
      (libsource (lib "eagle-import") (part "ACSL-60"))
    )
    (comp (ref "OK6")
      (value "ACSL-6310")
      (footprint "eagle-import:SO-16")
      (libsource (lib "eagle-import") (part "ACSL-60"))
    )
    (comp (ref "R5")
      (value "470")
      (footprint "eagle-import:R0603")
      (libsource (lib "eagle-import") (part "R-US_R0603"))
    )
    (comp (ref "R6")
      (value "470")
      (footprint "eagle-import:R0603")
      (libsource (lib "eagle-import") (part "R-US_R0603"))
    )
    (comp (ref "R21")
      (value "470")
      (footprint "eagle-import:R0603")
      (libsource (lib "eagle-import") (part "R-US_R0603"))
    )
    (comp (ref "R22")
      (value "470")
      (footprint "eagle-import:R0603")
      (libsource (lib "eagle-import") (part "R-US_R0603"))
    )
    (comp (ref "R23")
      (value "470")
      (footprint "eagle-import:R0603")
      (libsource (lib "eagle-import") (part "R-US_R0603"))
    )
    (comp (ref "R24")
      (value "470")
      (footprint "eagle-import:R0603")
      (libsource (lib "eagle-import") (part "R-US_R0603"))
    )
    (comp (ref "R25")
      (value "470")
      (footprint "eagle-import:R0603")
      (libsource (lib "eagle-import") (part "R-US_R0603"))
    )
    (comp (ref "R26")
      (value "470")
      (footprint "eagle-import:R0603")
      (libsource (lib "eagle-import") (part "R-US_R0603"))
    )
    (comp (ref "R45")
      (value "470")
      (footprint "eagle-import:R0603")
      (libsource (lib "eagle-import") (part "R-US_R0603"))
    )
    (comp (ref "R46")
      (value "470")
      (footprint "eagle-import:R0603")
      (libsource (lib "eagle-import") (part "R-US_R0603"))
    )
    (comp (ref "R47")
      (value "470")
      (footprint "eagle-import:R0603")
      (libsource (lib "eagle-import") (part "R-US_R0603"))
    )
    (comp (ref "R48")
      (value "470")
      (footprint "eagle-import:R0603")
      (libsource (lib "eagle-import") (part "R-US_R0603"))
    )
    (comp (ref "R49")
      (value "470")
      (footprint "eagle-import:R0603")
      (libsource (lib "eagle-import") (part "R-US_R0603"))
    )
    (comp (ref "R50")
      (value "470")
      (footprint "eagle-import:R0603")
      (libsource (lib "eagle-import") (part "R-US_R0603"))
    )
    (comp (ref "R69")
      (value "562")
      (footprint "eagle-import:R0603")
      (libsource (lib "eagle-import") (part "R-US_R0603"))
    )
    (comp (ref "R70")
      (value "133")
      (footprint "eagle-import:R0603")
      (libsource (lib "eagle-import") (part "R-US_R0603"))
    )
    (comp (ref "R71")
      (value "562")
      (footprint "eagle-import:R0603")
      (libsource (lib "eagle-import") (part "R-US_R0603"))
    )
    (comp (ref "R72")
      (value "562")
      (footprint "eagle-import:R0603")
      (libsource (lib "eagle-import") (part "R-US_R0603"))
    )
    (comp (ref "R73")
      (value "133")
      (footprint "eagle-import:R0603")
      (libsource (lib "eagle-import") (part "R-US_R0603"))
    )
    (comp (ref "R74")
      (value "562")
      (footprint "eagle-import:R0603")
      (libsource (lib "eagle-import") (part "R-US_R0603"))
    )
    (comp (ref "R89")
      (value "10")
      (footprint "eagle-import:R0603")
      (libsource (lib "eagle-import") (part "R-US_R0603"))
    )
    (comp (ref "R90")
      (value "10")
      (footprint "eagle-import:R0603")
      (libsource (lib "eagle-import") (part "R-US_R0603"))
    )
    (comp (ref "R91")
      (value "10")
      (footprint "eagle-import:R0603")
      (libsource (lib "eagle-import") (part "R-US_R0603"))
    )
    (comp (ref "R92")
      (value "10")
      (footprint "eagle-import:R0603")
      (libsource (lib "eagle-import") (part "R-US_R0603"))
    )
    (comp (ref "U5")
      (value "9V")
      (footprint "eagle-import:SOD323-NOSILK")
      (libsource (lib "eagle-import") (part "TVS-DIODESOD323-NOSILK"))
    )
    (comp (ref "U6")
      (value "9V")
      (footprint "eagle-import:SOD323-NOSILK")
      (libsource (lib "eagle-import") (part "TVS-DIODESOD323-NOSILK"))
    )
    (comp (ref "X5")
      (value "MPT3")
      (footprint "eagle-import:3POL254")
      (libsource (lib "eagle-import") (part "MPT3"))
    )
    (comp (ref "X6")
      (value "MPT3")
      (footprint "eagle-import:3POL254")
      (libsource (lib "eagle-import") (part "MPT3"))
    )
    (comp (ref "C57")
      (value "100u")
      (footprint "eagle-import:PANASONIC_D")
      (libsource (lib "eagle-import") (part "CPOL-USD"))
    )
    (comp (ref "C58")
      (value "470u")
      (footprint "eagle-import:PANASONIC_D")
      (libsource (lib "eagle-import") (part "CPOL-USD"))
    )
    (comp (ref "DC9")
      (value "SHHD003A0A")
      (footprint "eagle-import:SHHD003A0A")
      (libsource (lib "eagle-import") (part "SHHD003A0A"))
    )
    (comp (ref "J1")
      (value "M07")
      (footprint "eagle-import:1X07")
      (libsource (lib "eagle-import") (part "M07"))
    )
    (comp (ref "J2")
      (value "M07")
      (footprint "eagle-import:1X07")
      (libsource (lib "eagle-import") (part "M07"))
    )
    (comp (ref "J3")
      (value "A1")
      (footprint "eagle-import:1X10")
      (libsource (lib "eagle-import") (part "M10SILK_FEMALE_PTH"))
    )
    (comp (ref "J4")
      (value "B1")
      (footprint "eagle-import:1X10")
      (libsource (lib "eagle-import") (part "M10SILK_FEMALE_PTH"))
    )
    (comp (ref "J5")
      (value "A2")
      (footprint "eagle-import:1X10")
      (libsource (lib "eagle-import") (part "M10SILK_FEMALE_PTH"))
    )
    (comp (ref "J6")
      (value "B2")
      (footprint "eagle-import:1X10")
      (libsource (lib "eagle-import") (part "M10SILK_FEMALE_PTH"))
    )
    (comp (ref "J7")
      (value "M07")
      (footprint "eagle-import:1X07")
      (libsource (lib "eagle-import") (part "M07"))
    )
    (comp (ref "J8")
      (value "M07")
      (footprint "eagle-import:1X07")
      (libsource (lib "eagle-import") (part "M07"))
    )
    (comp (ref "J9")
      (value "M07")
      (footprint "eagle-import:1X07")
      (libsource (lib "eagle-import") (part "M07"))
    )
    (comp (ref "J10")
      (value "M07")
      (footprint "eagle-import:1X07")
      (libsource (lib "eagle-import") (part "M07"))
    )
    (comp (ref "J11")
      (value "C1")
      (footprint "eagle-import:1X10")
      (libsource (lib "eagle-import") (part "M10SILK_FEMALE_PTH"))
    )
    (comp (ref "J12")
      (value "D1")
      (footprint "eagle-import:1X10")
      (libsource (lib "eagle-import") (part "M10SILK_FEMALE_PTH"))
    )
    (comp (ref "J13")
      (value "C2")
      (footprint "eagle-import:1X10")
      (libsource (lib "eagle-import") (part "M10SILK_FEMALE_PTH"))
    )
    (comp (ref "J14")
      (value "D2")
      (footprint "eagle-import:1X10")
      (libsource (lib "eagle-import") (part "M10SILK_FEMALE_PTH"))
    )
    (comp (ref "J15")
      (value "M07")
      (footprint "eagle-import:1X07")
      (libsource (lib "eagle-import") (part "M07"))
    )
    (comp (ref "J16")
      (value "M07")
      (footprint "eagle-import:1X07")
      (libsource (lib "eagle-import") (part "M07"))
    )
    (comp (ref "J17")
      (value "M07")
      (footprint "eagle-import:1X07")
      (libsource (lib "eagle-import") (part "M07"))
    )
    (comp (ref "J18")
      (value "M07")
      (footprint "eagle-import:1X07")
      (libsource (lib "eagle-import") (part "M07"))
    )
    (comp (ref "J19")
      (value "M07")
      (footprint "eagle-import:1X07")
      (libsource (lib "eagle-import") (part "M07"))
    )
    (comp (ref "J20")
      (value "M07")
      (footprint "eagle-import:1X07")
      (libsource (lib "eagle-import") (part "M07"))
    )
    (comp (ref "J21")
      (value "M07")
      (footprint "eagle-import:1X07")
      (libsource (lib "eagle-import") (part "M07"))
    )
    (comp (ref "J22")
      (value "M07")
      (footprint "eagle-import:1X07")
      (libsource (lib "eagle-import") (part "M07"))
    )
    (comp (ref "R97")
      (value "4k7")
      (footprint "eagle-import:R0603")
      (libsource (lib "eagle-import") (part "R-US_R0603"))
    )
    (comp (ref "R98")
      (value "4k7")
      (footprint "eagle-import:R0603")
      (libsource (lib "eagle-import") (part "R-US_R0603"))
    )
    (comp (ref "X9")
      (value "MPT2")
      (footprint "eagle-import:2POL254")
      (libsource (lib "eagle-import") (part "MPT2"))
    )
    (comp (ref "X10")
      (value "MPT4")
      (footprint "eagle-import:4POL254")
      (libsource (lib "eagle-import") (part "MPT4"))
    )
    (comp (ref "X11")
      (value "MPT9")
      (footprint "eagle-import:9POL254")
      (libsource (lib "eagle-import") (part "MPT9"))
    )
    (comp (ref "C3")
      (value "10u")
      (footprint "eagle-import:E2,5-5-NOSILK")
      (libsource (lib "eagle-import") (part "CPOL-USE2.5-5-NOSILK"))
    )
    (comp (ref "C4")
      (value "10u")
      (footprint "eagle-import:E2,5-5-NOSILK")
      (libsource (lib "eagle-import") (part "CPOL-USE2.5-5-NOSILK"))
    )
    (comp (ref "C11")
      (value "0u1")
      (footprint "eagle-import:C0603K")
      (libsource (lib "eagle-import") (part "C-USC0603K"))
    )
    (comp (ref "C12")
      (value "0u1")
      (footprint "eagle-import:C0603K")
      (libsource (lib "eagle-import") (part "C-USC0603K"))
    )
    (comp (ref "C19")
      (value "10u")
      (footprint "eagle-import:C0603K")
      (libsource (lib "eagle-import") (part "C-USC0603K"))
    )
    (comp (ref "C20")
      (value "10u")
      (footprint "eagle-import:C0603K")
      (libsource (lib "eagle-import") (part "C-USC0603K"))
    )
    (comp (ref "C27")
      (value "10u")
      (footprint "eagle-import:C0603K")
      (libsource (lib "eagle-import") (part "C-USC0603K"))
    )
    (comp (ref "C28")
      (value "10u")
      (footprint "eagle-import:C0603K")
      (libsource (lib "eagle-import") (part "C-USC0603K"))
    )
    (comp (ref "C35")
      (value "10u")
      (footprint "eagle-import:C0603K")
      (libsource (lib "eagle-import") (part "C-USC0603K"))
    )
    (comp (ref "C36")
      (value "10u")
      (footprint "eagle-import:C0603K")
      (libsource (lib "eagle-import") (part "C-USC0603K"))
    )
    (comp (ref "C43")
      (value "0u1")
      (footprint "eagle-import:C0603K")
      (libsource (lib "eagle-import") (part "C-USC0603K"))
    )
    (comp (ref "C44")
      (value "0u1")
      (footprint "eagle-import:C0603K")
      (libsource (lib "eagle-import") (part "C-USC0603K"))
    )
    (comp (ref "C51")
      (value "0u1")
      (footprint "eagle-import:C0603K")
      (libsource (lib "eagle-import") (part "C-USC0603K"))
    )
    (comp (ref "C52")
      (value "0u1")
      (footprint "eagle-import:C0603K")
      (libsource (lib "eagle-import") (part "C-USC0603K"))
    )
    (comp (ref "D3")
      (value "LED0603")
      (footprint "eagle-import:LED-0603")
      (libsource (lib "eagle-import") (part "LED0603"))
    )
    (comp (ref "D4")
      (value "LED0603")
      (footprint "eagle-import:LED-0603")
      (libsource (lib "eagle-import") (part "LED0603"))
    )
    (comp (ref "D11")
      (value "LM712")
      (footprint "eagle-import:SOT23")
      (libsource (lib "eagle-import") (part "CDSOT23-SM712SOT23-STANDARD"))
    )
    (comp (ref "D12")
      (value "LM712")
      (footprint "eagle-import:SOT23")
      (libsource (lib "eagle-import") (part "CDSOT23-SM712SOT23-STANDARD"))
    )
    (comp (ref "DC3")
      (value "CRE1S0505S3C")
      (footprint "eagle-import:4SIL")
      (libsource (lib "eagle-import") (part "VA-?S0505"))
    )
    (comp (ref "DC4")
      (value "CRE1S0505S3C")
      (footprint "eagle-import:4SIL")
      (libsource (lib "eagle-import") (part "VA-?S0505"))
    )
    (comp (ref "F3")
      (value "PTC0603")
      (footprint "eagle-import:0603")
      (libsource (lib "eagle-import") (part "PTC0603"))
    )
    (comp (ref "F4")
      (value "PTC0603")
      (footprint "eagle-import:0603")
      (libsource (lib "eagle-import") (part "PTC0603"))
    )
    (comp (ref "IC3")
      (value "MAX481CSA")
      (footprint "eagle-import:SO08")
      (fields (field (name "MF") "MAXIM"))
      (libsource (lib "eagle-import") (part "MAX481CSA"))
    )
    (comp (ref "IC4")
      (value "MAX481CSA")
      (footprint "eagle-import:SO08")
      (fields (field (name "MF") "MAXIM"))
      (libsource (lib "eagle-import") (part "MAX481CSA"))
    )
    (comp (ref "OK3")
      (value "ACSL-6310")
      (footprint "eagle-import:SO-16")
      (libsource (lib "eagle-import") (part "ACSL-60"))
    )
    (comp (ref "OK4")
      (value "ACSL-6310")
      (footprint "eagle-import:SO-16")
      (libsource (lib "eagle-import") (part "ACSL-60"))
    )
    (comp (ref "R3")
      (value "470")
      (footprint "eagle-import:R0603")
      (libsource (lib "eagle-import") (part "R-US_R0603"))
    )
    (comp (ref "R4")
      (value "470")
      (footprint "eagle-import:R0603")
      (libsource (lib "eagle-import") (part "R-US_R0603"))
    )
    (comp (ref "R15")
      (value "470")
      (footprint "eagle-import:R0603")
      (libsource (lib "eagle-import") (part "R-US_R0603"))
    )
    (comp (ref "R16")
      (value "470")
      (footprint "eagle-import:R0603")
      (libsource (lib "eagle-import") (part "R-US_R0603"))
    )
    (comp (ref "R17")
      (value "470")
      (footprint "eagle-import:R0603")
      (libsource (lib "eagle-import") (part "R-US_R0603"))
    )
    (comp (ref "R18")
      (value "470")
      (footprint "eagle-import:R0603")
      (libsource (lib "eagle-import") (part "R-US_R0603"))
    )
    (comp (ref "R19")
      (value "470")
      (footprint "eagle-import:R0603")
      (libsource (lib "eagle-import") (part "R-US_R0603"))
    )
    (comp (ref "R20")
      (value "470")
      (footprint "eagle-import:R0603")
      (libsource (lib "eagle-import") (part "R-US_R0603"))
    )
    (comp (ref "R39")
      (value "470")
      (footprint "eagle-import:R0603")
      (libsource (lib "eagle-import") (part "R-US_R0603"))
    )
    (comp (ref "R40")
      (value "470")
      (footprint "eagle-import:R0603")
      (libsource (lib "eagle-import") (part "R-US_R0603"))
    )
    (comp (ref "R41")
      (value "470")
      (footprint "eagle-import:R0603")
      (libsource (lib "eagle-import") (part "R-US_R0603"))
    )
    (comp (ref "R42")
      (value "470")
      (footprint "eagle-import:R0603")
      (libsource (lib "eagle-import") (part "R-US_R0603"))
    )
    (comp (ref "R43")
      (value "470")
      (footprint "eagle-import:R0603")
      (libsource (lib "eagle-import") (part "R-US_R0603"))
    )
    (comp (ref "R44")
      (value "470")
      (footprint "eagle-import:R0603")
      (libsource (lib "eagle-import") (part "R-US_R0603"))
    )
    (comp (ref "R63")
      (value "562")
      (footprint "eagle-import:R0603")
      (libsource (lib "eagle-import") (part "R-US_R0603"))
    )
    (comp (ref "R64")
      (value "133")
      (footprint "eagle-import:R0603")
      (libsource (lib "eagle-import") (part "R-US_R0603"))
    )
    (comp (ref "R65")
      (value "562")
      (footprint "eagle-import:R0603")
      (libsource (lib "eagle-import") (part "R-US_R0603"))
    )
    (comp (ref "R66")
      (value "562")
      (footprint "eagle-import:R0603")
      (libsource (lib "eagle-import") (part "R-US_R0603"))
    )
    (comp (ref "R67")
      (value "133")
      (footprint "eagle-import:R0603")
      (libsource (lib "eagle-import") (part "R-US_R0603"))
    )
    (comp (ref "R68")
      (value "562")
      (footprint "eagle-import:R0603")
      (libsource (lib "eagle-import") (part "R-US_R0603"))
    )
    (comp (ref "R85")
      (value "10")
      (footprint "eagle-import:R0603")
      (libsource (lib "eagle-import") (part "R-US_R0603"))
    )
    (comp (ref "R86")
      (value "10")
      (footprint "eagle-import:R0603")
      (libsource (lib "eagle-import") (part "R-US_R0603"))
    )
    (comp (ref "R87")
      (value "10")
      (footprint "eagle-import:R0603")
      (libsource (lib "eagle-import") (part "R-US_R0603"))
    )
    (comp (ref "R88")
      (value "10")
      (footprint "eagle-import:R0603")
      (libsource (lib "eagle-import") (part "R-US_R0603"))
    )
    (comp (ref "U3")
      (value "9V")
      (footprint "eagle-import:SOD323-NOSILK")
      (libsource (lib "eagle-import") (part "TVS-DIODESOD323-NOSILK"))
    )
    (comp (ref "U4")
      (value "9V")
      (footprint "eagle-import:SOD323-NOSILK")
      (libsource (lib "eagle-import") (part "TVS-DIODESOD323-NOSILK"))
    )
    (comp (ref "X3")
      (value "MPT3")
      (footprint "eagle-import:3POL254")
      (libsource (lib "eagle-import") (part "MPT3"))
    )
    (comp (ref "X4")
      (value "MPT3")
      (footprint "eagle-import:3POL254")
      (libsource (lib "eagle-import") (part "MPT3"))
    )
  )
  (nets
    (net (code "1") (name "+3V3") (class "Default")
      (node (ref "J2") (pin "7") (pinfunction "7_7") (pintype "passive"))
      (node (ref "J21") (pin "1") (pinfunction "1_1") (pintype "passive"))
      (node (ref "J3") (pin "1") (pinfunction "1_1") (pintype "passive"))
      (node (ref "J5") (pin "1") (pinfunction "1_1") (pintype "passive"))
    )
    (net (code "2") (name "+5V-ISO1") (class "Default")
      (node (ref "C25") (pin "1") (pinfunction "1_1") (pintype "passive"))
      (node (ref "C33") (pin "1") (pinfunction "1_1") (pintype "passive"))
      (node (ref "C41") (pin "1") (pinfunction "1_1") (pintype "passive"))
      (node (ref "C49") (pin "1") (pinfunction "1_1") (pintype "passive"))
      (node (ref "DC1") (pin "4") (pinfunction "+VOUT_4") (pintype "passive"))
      (node (ref "IC1") (pin "8") (pinfunction "VCC_8") (pintype "power_in"))
      (node (ref "OK1") (pin "12") (pinfunction "VDD2_12") (pintype "power_in"))
      (node (ref "R33") (pin "1") (pinfunction "1_1") (pintype "passive"))
      (node (ref "R34") (pin "1") (pinfunction "1_1") (pintype "passive"))
      (node (ref "R35") (pin "1") (pinfunction "1_1") (pintype "passive"))
      (node (ref "R59") (pin "2") (pinfunction "2_2") (pintype "passive"))
    )
    (net (code "3") (name "+5V-ISO2") (class "Default")
      (node (ref "C26") (pin "1") (pinfunction "1_1") (pintype "passive"))
      (node (ref "C34") (pin "1") (pinfunction "1_1") (pintype "passive"))
      (node (ref "C42") (pin "1") (pinfunction "1_1") (pintype "passive"))
      (node (ref "C50") (pin "1") (pinfunction "1_1") (pintype "passive"))
      (node (ref "DC2") (pin "4") (pinfunction "+VOUT_4") (pintype "passive"))
      (node (ref "IC2") (pin "8") (pinfunction "VCC_8") (pintype "power_in"))
      (node (ref "OK2") (pin "12") (pinfunction "VDD2_12") (pintype "power_in"))
      (node (ref "R36") (pin "1") (pinfunction "1_1") (pintype "passive"))
      (node (ref "R37") (pin "1") (pinfunction "1_1") (pintype "passive"))
      (node (ref "R38") (pin "1") (pinfunction "1_1") (pintype "passive"))
      (node (ref "R62") (pin "2") (pinfunction "2_2") (pintype "passive"))
    )
    (net (code "4") (name "+5V-ISO3") (class "Default")
      (node (ref "C27") (pin "1") (pinfunction "1_1") (pintype "passive"))
      (node (ref "C35") (pin "1") (pinfunction "1_1") (pintype "passive"))
      (node (ref "C43") (pin "1") (pinfunction "1_1") (pintype "passive"))
      (node (ref "C51") (pin "1") (pinfunction "1_1") (pintype "passive"))
      (node (ref "DC3") (pin "4") (pinfunction "+VOUT_4") (pintype "passive"))
      (node (ref "IC3") (pin "8") (pinfunction "VCC_8") (pintype "power_in"))
      (node (ref "OK3") (pin "12") (pinfunction "VDD2_12") (pintype "power_in"))
      (node (ref "R39") (pin "1") (pinfunction "1_1") (pintype "passive"))
      (node (ref "R40") (pin "1") (pinfunction "1_1") (pintype "passive"))
      (node (ref "R41") (pin "1") (pinfunction "1_1") (pintype "passive"))
      (node (ref "R65") (pin "2") (pinfunction "2_2") (pintype "passive"))
    )
    (net (code "5") (name "+5V-ISO4") (class "Default")
      (node (ref "C28") (pin "1") (pinfunction "1_1") (pintype "passive"))
      (node (ref "C36") (pin "1") (pinfunction "1_1") (pintype "passive"))
      (node (ref "C44") (pin "1") (pinfunction "1_1") (pintype "passive"))
      (node (ref "C52") (pin "1") (pinfunction "1_1") (pintype "passive"))
      (node (ref "DC4") (pin "4") (pinfunction "+VOUT_4") (pintype "passive"))
      (node (ref "IC4") (pin "8") (pinfunction "VCC_8") (pintype "power_in"))
      (node (ref "OK4") (pin "12") (pinfunction "VDD2_12") (pintype "power_in"))
      (node (ref "R42") (pin "1") (pinfunction "1_1") (pintype "passive"))
      (node (ref "R43") (pin "1") (pinfunction "1_1") (pintype "passive"))
      (node (ref "R44") (pin "1") (pinfunction "1_1") (pintype "passive"))
      (node (ref "R68") (pin "2") (pinfunction "2_2") (pintype "passive"))
    )
    (net (code "6") (name "+5V-ISO5") (class "Default")
      (node (ref "C29") (pin "1") (pinfunction "1_1") (pintype "passive"))
      (node (ref "C37") (pin "1") (pinfunction "1_1") (pintype "passive"))
      (node (ref "C45") (pin "1") (pinfunction "1_1") (pintype "passive"))
      (node (ref "C53") (pin "1") (pinfunction "1_1") (pintype "passive"))
      (node (ref "DC5") (pin "4") (pinfunction "+VOUT_4") (pintype "passive"))
      (node (ref "IC5") (pin "8") (pinfunction "VCC_8") (pintype "power_in"))
      (node (ref "OK5") (pin "12") (pinfunction "VDD2_12") (pintype "power_in"))
      (node (ref "R45") (pin "1") (pinfunction "1_1") (pintype "passive"))
      (node (ref "R46") (pin "1") (pinfunction "1_1") (pintype "passive"))
      (node (ref "R47") (pin "1") (pinfunction "1_1") (pintype "passive"))
      (node (ref "R71") (pin "2") (pinfunction "2_2") (pintype "passive"))
    )
    (net (code "7") (name "+5V-ISO6") (class "Default")
      (node (ref "C30") (pin "1") (pinfunction "1_1") (pintype "passive"))
      (node (ref "C38") (pin "1") (pinfunction "1_1") (pintype "passive"))
      (node (ref "C46") (pin "1") (pinfunction "1_1") (pintype "passive"))
      (node (ref "C54") (pin "1") (pinfunction "1_1") (pintype "passive"))
      (node (ref "DC6") (pin "4") (pinfunction "+VOUT_4") (pintype "passive"))
      (node (ref "IC6") (pin "8") (pinfunction "VCC_8") (pintype "power_in"))
      (node (ref "OK6") (pin "12") (pinfunction "VDD2_12") (pintype "power_in"))
      (node (ref "R48") (pin "1") (pinfunction "1_1") (pintype "passive"))
      (node (ref "R49") (pin "1") (pinfunction "1_1") (pintype "passive"))
      (node (ref "R50") (pin "1") (pinfunction "1_1") (pintype "passive"))
      (node (ref "R74") (pin "2") (pinfunction "2_2") (pintype "passive"))
    )
    (net (code "8") (name "+5V-ISO7") (class "Default")
      (node (ref "C31") (pin "1") (pinfunction "1_1") (pintype "passive"))
      (node (ref "C39") (pin "1") (pinfunction "1_1") (pintype "passive"))
      (node (ref "C47") (pin "1") (pinfunction "1_1") (pintype "passive"))
      (node (ref "C55") (pin "1") (pinfunction "1_1") (pintype "passive"))
      (node (ref "DC7") (pin "4") (pinfunction "+VOUT_4") (pintype "passive"))
      (node (ref "IC7") (pin "8") (pinfunction "VCC_8") (pintype "power_in"))
      (node (ref "OK7") (pin "12") (pinfunction "VDD2_12") (pintype "power_in"))
      (node (ref "R51") (pin "1") (pinfunction "1_1") (pintype "passive"))
      (node (ref "R52") (pin "1") (pinfunction "1_1") (pintype "passive"))
      (node (ref "R53") (pin "1") (pinfunction "1_1") (pintype "passive"))
      (node (ref "R77") (pin "2") (pinfunction "2_2") (pintype "passive"))
    )
    (net (code "9") (name "+5V-ISO8") (class "Default")
      (node (ref "C32") (pin "1") (pinfunction "1_1") (pintype "passive"))
      (node (ref "C40") (pin "1") (pinfunction "1_1") (pintype "passive"))
      (node (ref "C48") (pin "1") (pinfunction "1_1") (pintype "passive"))
      (node (ref "C56") (pin "1") (pinfunction "1_1") (pintype "passive"))
      (node (ref "DC8") (pin "4") (pinfunction "+VOUT_4") (pintype "passive"))
      (node (ref "IC8") (pin "8") (pinfunction "VCC_8") (pintype "power_in"))
      (node (ref "OK8") (pin "12") (pinfunction "VDD2_12") (pintype "power_in"))
      (node (ref "R54") (pin "1") (pinfunction "1_1") (pintype "passive"))
      (node (ref "R55") (pin "1") (pinfunction "1_1") (pintype "passive"))
      (node (ref "R56") (pin "1") (pinfunction "1_1") (pintype "passive"))
      (node (ref "R80") (pin "2") (pinfunction "2_2") (pintype "passive"))
    )
    (net (code "10") (name "5V") (class "Default")
      (node (ref "C58") (pin "+") (pinfunction "+_+") (pintype "passive"))
      (node (ref "DC9") (pin "4") (pinfunction "VOUT+_4") (pintype "power_in"))
      (node (ref "F1") (pin "1") (pinfunction "1_1") (pintype "bidirectional"))
      (node (ref "F2") (pin "1") (pinfunction "1_1") (pintype "bidirectional"))
      (node (ref "F3") (pin "1") (pinfunction "1_1") (pintype "bidirectional"))
      (node (ref "F4") (pin "1") (pinfunction "1_1") (pintype "bidirectional"))
      (node (ref "F5") (pin "1") (pinfunction "1_1") (pintype "bidirectional"))
      (node (ref "F6") (pin "1") (pinfunction "1_1") (pintype "bidirectional"))
      (node (ref "F7") (pin "1") (pinfunction "1_1") (pintype "bidirectional"))
      (node (ref "F8") (pin "1") (pinfunction "1_1") (pintype "bidirectional"))
      (node (ref "J1") (pin "7") (pinfunction "7_7") (pintype "passive"))
      (node (ref "J22") (pin "1") (pinfunction "1_1") (pintype "passive"))
      (node (ref "J4") (pin "1") (pinfunction "1_1") (pintype "passive"))
      (node (ref "J6") (pin "1") (pinfunction "1_1") (pintype "passive"))
      (node (ref "R97") (pin "2") (pinfunction "2_2") (pintype "passive"))
      (node (ref "R98") (pin "2") (pinfunction "2_2") (pintype "passive"))
      (node (ref "X10") (pin "4") (pinfunction "1_4") (pintype "passive"))
    )
    (net (code "11") (name "GND") (class "Default")
      (node (ref "C1") (pin "-") (pinfunction "-_-") (pintype "passive"))
      (node (ref "C10") (pin "2") (pinfunction "2_2") (pintype "passive"))
      (node (ref "C11") (pin "2") (pinfunction "2_2") (pintype "passive"))
      (node (ref "C12") (pin "2") (pinfunction "2_2") (pintype "passive"))
      (node (ref "C13") (pin "2") (pinfunction "2_2") (pintype "passive"))
      (node (ref "C14") (pin "2") (pinfunction "2_2") (pintype "passive"))
      (node (ref "C15") (pin "2") (pinfunction "2_2") (pintype "passive"))
      (node (ref "C16") (pin "2") (pinfunction "2_2") (pintype "passive"))
      (node (ref "C17") (pin "2") (pinfunction "2_2") (pintype "passive"))
      (node (ref "C18") (pin "2") (pinfunction "2_2") (pintype "passive"))
      (node (ref "C19") (pin "2") (pinfunction "2_2") (pintype "passive"))
      (node (ref "C2") (pin "-") (pinfunction "-_-") (pintype "passive"))
      (node (ref "C20") (pin "2") (pinfunction "2_2") (pintype "passive"))
      (node (ref "C21") (pin "2") (pinfunction "2_2") (pintype "passive"))
      (node (ref "C22") (pin "2") (pinfunction "2_2") (pintype "passive"))
      (node (ref "C23") (pin "2") (pinfunction "2_2") (pintype "passive"))
      (node (ref "C24") (pin "2") (pinfunction "2_2") (pintype "passive"))
      (node (ref "C3") (pin "-") (pinfunction "-_-") (pintype "passive"))
      (node (ref "C4") (pin "-") (pinfunction "-_-") (pintype "passive"))
      (node (ref "C5") (pin "-") (pinfunction "-_-") (pintype "passive"))
      (node (ref "C58") (pin "-") (pinfunction "-_-") (pintype "passive"))
      (node (ref "C6") (pin "-") (pinfunction "-_-") (pintype "passive"))
      (node (ref "C7") (pin "-") (pinfunction "-_-") (pintype "passive"))
      (node (ref "C8") (pin "-") (pinfunction "-_-") (pintype "passive"))
      (node (ref "C9") (pin "2") (pinfunction "2_2") (pintype "passive"))
      (node (ref "DC1") (pin "1") (pinfunction "-VIN_1") (pintype "passive"))
      (node (ref "DC2") (pin "1") (pinfunction "-VIN_1") (pintype "passive"))
      (node (ref "DC3") (pin "1") (pinfunction "-VIN_1") (pintype "passive"))
      (node (ref "DC4") (pin "1") (pinfunction "-VIN_1") (pintype "passive"))
      (node (ref "DC5") (pin "1") (pinfunction "-VIN_1") (pintype "passive"))
      (node (ref "DC6") (pin "1") (pinfunction "-VIN_1") (pintype "passive"))
      (node (ref "DC7") (pin "1") (pinfunction "-VIN_1") (pintype "passive"))
      (node (ref "DC8") (pin "1") (pinfunction "-VIN_1") (pintype "passive"))
      (node (ref "DC9") (pin "6") (pinfunction "VOUT-_6") (pintype "power_in"))
      (node (ref "J10") (pin "3") (pinfunction "3_3") (pintype "passive"))
      (node (ref "J12") (pin "1") (pinfunction "1_1") (pintype "passive"))
      (node (ref "J14") (pin "1") (pinfunction "1_1") (pintype "passive"))
      (node (ref "J17") (pin "4") (pinfunction "4_4") (pintype "passive"))
      (node (ref "J18") (pin "4") (pinfunction "4_4") (pintype "passive"))
      (node (ref "J2") (pin "6") (pinfunction "6_6") (pintype "passive"))
      (node (ref "J21") (pin "2") (pinfunction "2_2") (pintype "passive"))
      (node (ref "J22") (pin "2") (pinfunction "2_2") (pintype "passive"))
      (node (ref "J4") (pin "2") (pinfunction "2_2") (pintype "passive"))
      (node (ref "J6") (pin "2") (pinfunction "2_2") (pintype "passive"))
      (node (ref "J9") (pin "3") (pinfunction "3_3") (pintype "passive"))
      (node (ref "OK1") (pin "1") (pinfunction "GND1_1") (pintype "power_in"))
      (node (ref "OK2") (pin "1") (pinfunction "GND1_1") (pintype "power_in"))
      (node (ref "OK3") (pin "1") (pinfunction "GND1_1") (pintype "power_in"))
      (node (ref "OK4") (pin "1") (pinfunction "GND1_1") (pintype "power_in"))
      (node (ref "OK5") (pin "1") (pinfunction "GND1_1") (pintype "power_in"))
      (node (ref "OK6") (pin "1") (pinfunction "GND1_1") (pintype "power_in"))
      (node (ref "OK7") (pin "1") (pinfunction "GND1_1") (pintype "power_in"))
      (node (ref "OK8") (pin "1") (pinfunction "GND1_1") (pintype "power_in"))
      (node (ref "R1") (pin "2") (pinfunction "2_2") (pintype "passive"))
      (node (ref "R2") (pin "2") (pinfunction "2_2") (pintype "passive"))
      (node (ref "R3") (pin "2") (pinfunction "2_2") (pintype "passive"))
      (node (ref "R4") (pin "2") (pinfunction "2_2") (pintype "passive"))
      (node (ref "R5") (pin "2") (pinfunction "2_2") (pintype "passive"))
      (node (ref "R6") (pin "2") (pinfunction "2_2") (pintype "passive"))
      (node (ref "R7") (pin "2") (pinfunction "2_2") (pintype "passive"))
      (node (ref "R8") (pin "2") (pinfunction "2_2") (pintype "passive"))
      (node (ref "U1") (pin "A") (pinfunction "A_A") (pintype "passive"))
      (node (ref "U2") (pin "A") (pinfunction "A_A") (pintype "passive"))
      (node (ref "U3") (pin "A") (pinfunction "A_A") (pintype "passive"))
      (node (ref "U4") (pin "A") (pinfunction "A_A") (pintype "passive"))
      (node (ref "U5") (pin "A") (pinfunction "A_A") (pintype "passive"))
      (node (ref "U6") (pin "A") (pinfunction "A_A") (pintype "passive"))
      (node (ref "U7") (pin "A") (pinfunction "A_A") (pintype "passive"))
      (node (ref "U8") (pin "A") (pinfunction "A_A") (pintype "passive"))
      (node (ref "X10") (pin "1") (pinfunction "1_1") (pintype "passive"))
      (node (ref "X11") (pin "1") (pinfunction "1_1") (pintype "passive"))
    )
    (net (code "12") (name "GND-ISO1") (class "Default")
      (node (ref "C25") (pin "2") (pinfunction "2_2") (pintype "passive"))
      (node (ref "C33") (pin "2") (pinfunction "2_2") (pintype "passive"))
      (node (ref "C41") (pin "2") (pinfunction "2_2") (pintype "passive"))
      (node (ref "C49") (pin "2") (pinfunction "2_2") (pintype "passive"))
      (node (ref "D9") (pin "3") (pinfunction "3_3") (pintype "passive"))
      (node (ref "DC1") (pin "3") (pinfunction "-VOUT_3") (pintype "passive"))
      (node (ref "IC1") (pin "5") (pinfunction "GND_5") (pintype "power_in"))
      (node (ref "OK1") (pin "9") (pinfunction "GND2_9") (pintype "power_in"))
      (node (ref "R57") (pin "1") (pinfunction "1_1") (pintype "passive"))
      (node (ref "X1") (pin "1") (pinfunction "1_1") (pintype "passive"))
    )
    (net (code "13") (name "GND-ISO2") (class "Default")
      (node (ref "C26") (pin "2") (pinfunction "2_2") (pintype "passive"))
      (node (ref "C34") (pin "2") (pinfunction "2_2") (pintype "passive"))
      (node (ref "C42") (pin "2") (pinfunction "2_2") (pintype "passive"))
      (node (ref "C50") (pin "2") (pinfunction "2_2") (pintype "passive"))
      (node (ref "D10") (pin "3") (pinfunction "3_3") (pintype "passive"))
      (node (ref "DC2") (pin "3") (pinfunction "-VOUT_3") (pintype "passive"))
      (node (ref "IC2") (pin "5") (pinfunction "GND_5") (pintype "power_in"))
      (node (ref "OK2") (pin "9") (pinfunction "GND2_9") (pintype "power_in"))
      (node (ref "R60") (pin "1") (pinfunction "1_1") (pintype "passive"))
      (node (ref "X2") (pin "1") (pinfunction "1_1") (pintype "passive"))
    )
    (net (code "14") (name "GND-ISO3") (class "Default")
      (node (ref "C27") (pin "2") (pinfunction "2_2") (pintype "passive"))
      (node (ref "C35") (pin "2") (pinfunction "2_2") (pintype "passive"))
      (node (ref "C43") (pin "2") (pinfunction "2_2") (pintype "passive"))
      (node (ref "C51") (pin "2") (pinfunction "2_2") (pintype "passive"))
      (node (ref "D11") (pin "3") (pinfunction "3_3") (pintype "passive"))
      (node (ref "DC3") (pin "3") (pinfunction "-VOUT_3") (pintype "passive"))
      (node (ref "IC3") (pin "5") (pinfunction "GND_5") (pintype "power_in"))
      (node (ref "OK3") (pin "9") (pinfunction "GND2_9") (pintype "power_in"))
      (node (ref "R63") (pin "1") (pinfunction "1_1") (pintype "passive"))
      (node (ref "X3") (pin "1") (pinfunction "1_1") (pintype "passive"))
    )
    (net (code "15") (name "GND-ISO4") (class "Default")
      (node (ref "C28") (pin "2") (pinfunction "2_2") (pintype "passive"))
      (node (ref "C36") (pin "2") (pinfunction "2_2") (pintype "passive"))
      (node (ref "C44") (pin "2") (pinfunction "2_2") (pintype "passive"))
      (node (ref "C52") (pin "2") (pinfunction "2_2") (pintype "passive"))
      (node (ref "D12") (pin "3") (pinfunction "3_3") (pintype "passive"))
      (node (ref "DC4") (pin "3") (pinfunction "-VOUT_3") (pintype "passive"))
      (node (ref "IC4") (pin "5") (pinfunction "GND_5") (pintype "power_in"))
      (node (ref "OK4") (pin "9") (pinfunction "GND2_9") (pintype "power_in"))
      (node (ref "R66") (pin "1") (pinfunction "1_1") (pintype "passive"))
      (node (ref "X4") (pin "1") (pinfunction "1_1") (pintype "passive"))
    )
    (net (code "16") (name "GND-ISO5") (class "Default")
      (node (ref "C29") (pin "2") (pinfunction "2_2") (pintype "passive"))
      (node (ref "C37") (pin "2") (pinfunction "2_2") (pintype "passive"))
      (node (ref "C45") (pin "2") (pinfunction "2_2") (pintype "passive"))
      (node (ref "C53") (pin "2") (pinfunction "2_2") (pintype "passive"))
      (node (ref "D13") (pin "3") (pinfunction "3_3") (pintype "passive"))
      (node (ref "DC5") (pin "3") (pinfunction "-VOUT_3") (pintype "passive"))
      (node (ref "IC5") (pin "5") (pinfunction "GND_5") (pintype "power_in"))
      (node (ref "OK5") (pin "9") (pinfunction "GND2_9") (pintype "power_in"))
      (node (ref "R69") (pin "1") (pinfunction "1_1") (pintype "passive"))
      (node (ref "X5") (pin "1") (pinfunction "1_1") (pintype "passive"))
    )
    (net (code "17") (name "GND-ISO6") (class "Default")
      (node (ref "C30") (pin "2") (pinfunction "2_2") (pintype "passive"))
      (node (ref "C38") (pin "2") (pinfunction "2_2") (pintype "passive"))
      (node (ref "C46") (pin "2") (pinfunction "2_2") (pintype "passive"))
      (node (ref "C54") (pin "2") (pinfunction "2_2") (pintype "passive"))
      (node (ref "D14") (pin "3") (pinfunction "3_3") (pintype "passive"))
      (node (ref "DC6") (pin "3") (pinfunction "-VOUT_3") (pintype "passive"))
      (node (ref "IC6") (pin "5") (pinfunction "GND_5") (pintype "power_in"))
      (node (ref "OK6") (pin "9") (pinfunction "GND2_9") (pintype "power_in"))
      (node (ref "R72") (pin "1") (pinfunction "1_1") (pintype "passive"))
      (node (ref "X6") (pin "1") (pinfunction "1_1") (pintype "passive"))
    )
    (net (code "18") (name "GND-ISO7") (class "Default")
      (node (ref "C31") (pin "2") (pinfunction "2_2") (pintype "passive"))
      (node (ref "C39") (pin "2") (pinfunction "2_2") (pintype "passive"))
      (node (ref "C47") (pin "2") (pinfunction "2_2") (pintype "passive"))
      (node (ref "C55") (pin "2") (pinfunction "2_2") (pintype "passive"))
      (node (ref "D15") (pin "3") (pinfunction "3_3") (pintype "passive"))
      (node (ref "DC7") (pin "3") (pinfunction "-VOUT_3") (pintype "passive"))
      (node (ref "IC7") (pin "5") (pinfunction "GND_5") (pintype "power_in"))
      (node (ref "OK7") (pin "9") (pinfunction "GND2_9") (pintype "power_in"))
      (node (ref "R75") (pin "1") (pinfunction "1_1") (pintype "passive"))
      (node (ref "X7") (pin "1") (pinfunction "1_1") (pintype "passive"))
    )
    (net (code "19") (name "GND-ISO8") (class "Default")
      (node (ref "C32") (pin "2") (pinfunction "2_2") (pintype "passive"))
      (node (ref "C40") (pin "2") (pinfunction "2_2") (pintype "passive"))
      (node (ref "C48") (pin "2") (pinfunction "2_2") (pintype "passive"))
      (node (ref "C56") (pin "2") (pinfunction "2_2") (pintype "passive"))
      (node (ref "D16") (pin "3") (pinfunction "3_3") (pintype "passive"))
      (node (ref "DC8") (pin "3") (pinfunction "-VOUT_3") (pintype "passive"))
      (node (ref "IC8") (pin "5") (pinfunction "GND_5") (pintype "power_in"))
      (node (ref "OK8") (pin "9") (pinfunction "GND2_9") (pintype "power_in"))
      (node (ref "R78") (pin "1") (pinfunction "1_1") (pintype "passive"))
      (node (ref "X8") (pin "1") (pinfunction "1_1") (pintype "passive"))
    )
    (net (code "20") (name "I2C0-SCL") (class "Default")
      (node (ref "R98") (pin "1") (pinfunction "1_1") (pintype "passive"))
      (node (ref "X10") (pin "2") (pinfunction "1_2") (pintype "passive"))
    )
    (net (code "21") (name "I2C0-SDA") (class "Default")
      (node (ref "R97") (pin "1") (pinfunction "1_1") (pintype "passive"))
      (node (ref "X10") (pin "3") (pinfunction "1_3") (pintype "passive"))
    )
    (net (code "22") (name "Net-(D1-PadC)") (class "Default")
      (node (ref "D1") (pin "C") (pinfunction "C_C") (pintype "passive"))
      (node (ref "R1") (pin "1") (pinfunction "1_1") (pintype "passive"))
    )
    (net (code "23") (name "Net-(D2-PadC)") (class "Default")
      (node (ref "D2") (pin "C") (pinfunction "C_C") (pintype "passive"))
      (node (ref "R2") (pin "1") (pinfunction "1_1") (pintype "passive"))
    )
    (net (code "24") (name "Net-(D3-PadC)") (class "Default")
      (node (ref "D3") (pin "C") (pinfunction "C_C") (pintype "passive"))
      (node (ref "R3") (pin "1") (pinfunction "1_1") (pintype "passive"))
    )
    (net (code "25") (name "Net-(D4-PadC)") (class "Default")
      (node (ref "D4") (pin "C") (pinfunction "C_C") (pintype "passive"))
      (node (ref "R4") (pin "1") (pinfunction "1_1") (pintype "passive"))
    )
    (net (code "26") (name "Net-(D5-PadC)") (class "Default")
      (node (ref "D5") (pin "C") (pinfunction "C_C") (pintype "passive"))
      (node (ref "R5") (pin "1") (pinfunction "1_1") (pintype "passive"))
    )
    (net (code "27") (name "Net-(D6-PadC)") (class "Default")
      (node (ref "D6") (pin "C") (pinfunction "C_C") (pintype "passive"))
      (node (ref "R6") (pin "1") (pinfunction "1_1") (pintype "passive"))
    )
    (net (code "28") (name "Net-(D7-PadC)") (class "Default")
      (node (ref "D7") (pin "C") (pinfunction "C_C") (pintype "passive"))
      (node (ref "R7") (pin "1") (pinfunction "1_1") (pintype "passive"))
    )
    (net (code "29") (name "Net-(D8-PadC)") (class "Default")
      (node (ref "D8") (pin "C") (pinfunction "C_C") (pintype "passive"))
      (node (ref "R8") (pin "1") (pinfunction "1_1") (pintype "passive"))
    )
    (net (code "30") (name "Net-(DC9-VIN+)") (class "Default")
      (node (ref "C57") (pin "+") (pinfunction "+_+") (pintype "passive"))
      (node (ref "DC9") (pin "3") (pinfunction "VIN+_3") (pintype "input"))
      (node (ref "X9") (pin "1") (pinfunction "1_1") (pintype "passive"))
    )
    (net (code "31") (name "Net-(DC9-VIN-)") (class "Default")
      (node (ref "C57") (pin "-") (pinfunction "-_-") (pintype "passive"))
      (node (ref "DC9") (pin "1") (pinfunction "VIN-_1") (pintype "input"))
      (node (ref "X9") (pin "2") (pinfunction "1_2") (pintype "passive"))
    )
    (net (code "32") (name "Net-(IC1A-A)") (class "Default")
      (node (ref "IC1") (pin "6") (pinfunction "A_6") (pintype "passive"))
      (node (ref "R58") (pin "2") (pinfunction "2_2") (pintype "passive"))
      (node (ref "R59") (pin "1") (pinfunction "1_1") (pintype "passive"))
      (node (ref "R82") (pin "1") (pinfunction "1_1") (pintype "passive"))
    )
    (net (code "33") (name "Net-(IC1A-B)") (class "Default")
      (node (ref "IC1") (pin "7") (pinfunction "B_7") (pintype "passive"))
      (node (ref "R57") (pin "2") (pinfunction "2_2") (pintype "passive"))
      (node (ref "R58") (pin "1") (pinfunction "1_1") (pintype "passive"))
      (node (ref "R81") (pin "1") (pinfunction "1_1") (pintype "passive"))
    )
    (net (code "34") (name "Net-(IC1A-DE)") (class "Default")
      (node (ref "IC1") (pin "2") (pinfunction "RE/_2") (pintype "input"))
      (node (ref "IC1") (pin "3") (pinfunction "DE_3") (pintype "input"))
      (node (ref "OK1") (pin "11") (pinfunction "VO1_11") (pintype "output"))
      (node (ref "R34") (pin "2") (pinfunction "2_2") (pintype "passive"))
    )
    (net (code "35") (name "Net-(IC1A-DI)") (class "Default")
      (node (ref "IC1") (pin "4") (pinfunction "DI_4") (pintype "input"))
      (node (ref "OK1") (pin "10") (pinfunction "VO2_10") (pintype "output"))
      (node (ref "R35") (pin "2") (pinfunction "2_2") (pintype "passive"))
    )
    (net (code "36") (name "Net-(IC1A-RO)") (class "Default")
      (node (ref "IC1") (pin "1") (pinfunction "RO_1") (pintype "output"))
      (node (ref "OK1") (pin "13") (pinfunction "C3_13") (pintype "passive"))
    )
    (net (code "37") (name "Net-(IC2A-A)") (class "Default")
      (node (ref "IC2") (pin "6") (pinfunction "A_6") (pintype "passive"))
      (node (ref "R61") (pin "2") (pinfunction "2_2") (pintype "passive"))
      (node (ref "R62") (pin "1") (pinfunction "1_1") (pintype "passive"))
      (node (ref "R84") (pin "1") (pinfunction "1_1") (pintype "passive"))
    )
    (net (code "38") (name "Net-(IC2A-B)") (class "Default")
      (node (ref "IC2") (pin "7") (pinfunction "B_7") (pintype "passive"))
      (node (ref "R60") (pin "2") (pinfunction "2_2") (pintype "passive"))
      (node (ref "R61") (pin "1") (pinfunction "1_1") (pintype "passive"))
      (node (ref "R83") (pin "1") (pinfunction "1_1") (pintype "passive"))
    )
    (net (code "39") (name "Net-(IC2A-DE)") (class "Default")
      (node (ref "IC2") (pin "2") (pinfunction "RE/_2") (pintype "input"))
      (node (ref "IC2") (pin "3") (pinfunction "DE_3") (pintype "input"))
      (node (ref "OK2") (pin "11") (pinfunction "VO1_11") (pintype "output"))
      (node (ref "R37") (pin "2") (pinfunction "2_2") (pintype "passive"))
    )
    (net (code "40") (name "Net-(IC2A-DI)") (class "Default")
      (node (ref "IC2") (pin "4") (pinfunction "DI_4") (pintype "input"))
      (node (ref "OK2") (pin "10") (pinfunction "VO2_10") (pintype "output"))
      (node (ref "R38") (pin "2") (pinfunction "2_2") (pintype "passive"))
    )
    (net (code "41") (name "Net-(IC2A-RO)") (class "Default")
      (node (ref "IC2") (pin "1") (pinfunction "RO_1") (pintype "output"))
      (node (ref "OK2") (pin "13") (pinfunction "C3_13") (pintype "passive"))
    )
    (net (code "42") (name "Net-(IC3A-A)") (class "Default")
      (node (ref "IC3") (pin "6") (pinfunction "A_6") (pintype "passive"))
      (node (ref "R64") (pin "2") (pinfunction "2_2") (pintype "passive"))
      (node (ref "R65") (pin "1") (pinfunction "1_1") (pintype "passive"))
      (node (ref "R86") (pin "1") (pinfunction "1_1") (pintype "passive"))
    )
    (net (code "43") (name "Net-(IC3A-B)") (class "Default")
      (node (ref "IC3") (pin "7") (pinfunction "B_7") (pintype "passive"))
      (node (ref "R63") (pin "2") (pinfunction "2_2") (pintype "passive"))
      (node (ref "R64") (pin "1") (pinfunction "1_1") (pintype "passive"))
      (node (ref "R85") (pin "1") (pinfunction "1_1") (pintype "passive"))
    )
    (net (code "44") (name "Net-(IC3A-DE)") (class "Default")
      (node (ref "IC3") (pin "2") (pinfunction "RE/_2") (pintype "input"))
      (node (ref "IC3") (pin "3") (pinfunction "DE_3") (pintype "input"))
      (node (ref "OK3") (pin "11") (pinfunction "VO1_11") (pintype "output"))
      (node (ref "R40") (pin "2") (pinfunction "2_2") (pintype "passive"))
    )
    (net (code "45") (name "Net-(IC3A-DI)") (class "Default")
      (node (ref "IC3") (pin "4") (pinfunction "DI_4") (pintype "input"))
      (node (ref "OK3") (pin "10") (pinfunction "VO2_10") (pintype "output"))
      (node (ref "R41") (pin "2") (pinfunction "2_2") (pintype "passive"))
    )
    (net (code "46") (name "Net-(IC3A-RO)") (class "Default")
      (node (ref "IC3") (pin "1") (pinfunction "RO_1") (pintype "output"))
      (node (ref "OK3") (pin "13") (pinfunction "C3_13") (pintype "passive"))
    )
    (net (code "47") (name "Net-(IC4A-A)") (class "Default")
      (node (ref "IC4") (pin "6") (pinfunction "A_6") (pintype "passive"))
      (node (ref "R67") (pin "2") (pinfunction "2_2") (pintype "passive"))
      (node (ref "R68") (pin "1") (pinfunction "1_1") (pintype "passive"))
      (node (ref "R88") (pin "1") (pinfunction "1_1") (pintype "passive"))
    )
    (net (code "48") (name "Net-(IC4A-B)") (class "Default")
      (node (ref "IC4") (pin "7") (pinfunction "B_7") (pintype "passive"))
      (node (ref "R66") (pin "2") (pinfunction "2_2") (pintype "passive"))
      (node (ref "R67") (pin "1") (pinfunction "1_1") (pintype "passive"))
      (node (ref "R87") (pin "1") (pinfunction "1_1") (pintype "passive"))
    )
    (net (code "49") (name "Net-(IC4A-DE)") (class "Default")
      (node (ref "IC4") (pin "2") (pinfunction "RE/_2") (pintype "input"))
      (node (ref "IC4") (pin "3") (pinfunction "DE_3") (pintype "input"))
      (node (ref "OK4") (pin "11") (pinfunction "VO1_11") (pintype "output"))
      (node (ref "R43") (pin "2") (pinfunction "2_2") (pintype "passive"))
    )
    (net (code "50") (name "Net-(IC4A-DI)") (class "Default")
      (node (ref "IC4") (pin "4") (pinfunction "DI_4") (pintype "input"))
      (node (ref "OK4") (pin "10") (pinfunction "VO2_10") (pintype "output"))
      (node (ref "R44") (pin "2") (pinfunction "2_2") (pintype "passive"))
    )
    (net (code "51") (name "Net-(IC4A-RO)") (class "Default")
      (node (ref "IC4") (pin "1") (pinfunction "RO_1") (pintype "output"))
      (node (ref "OK4") (pin "13") (pinfunction "C3_13") (pintype "passive"))
    )
    (net (code "52") (name "Net-(IC5A-A)") (class "Default")
      (node (ref "IC5") (pin "6") (pinfunction "A_6") (pintype "passive"))
      (node (ref "R70") (pin "2") (pinfunction "2_2") (pintype "passive"))
      (node (ref "R71") (pin "1") (pinfunction "1_1") (pintype "passive"))
      (node (ref "R90") (pin "1") (pinfunction "1_1") (pintype "passive"))
    )
    (net (code "53") (name "Net-(IC5A-B)") (class "Default")
      (node (ref "IC5") (pin "7") (pinfunction "B_7") (pintype "passive"))
      (node (ref "R69") (pin "2") (pinfunction "2_2") (pintype "passive"))
      (node (ref "R70") (pin "1") (pinfunction "1_1") (pintype "passive"))
      (node (ref "R89") (pin "1") (pinfunction "1_1") (pintype "passive"))
    )
    (net (code "54") (name "Net-(IC5A-DE)") (class "Default")
      (node (ref "IC5") (pin "2") (pinfunction "RE/_2") (pintype "input"))
      (node (ref "IC5") (pin "3") (pinfunction "DE_3") (pintype "input"))
      (node (ref "OK5") (pin "11") (pinfunction "VO1_11") (pintype "output"))
      (node (ref "R46") (pin "2") (pinfunction "2_2") (pintype "passive"))
    )
    (net (code "55") (name "Net-(IC5A-DI)") (class "Default")
      (node (ref "IC5") (pin "4") (pinfunction "DI_4") (pintype "input"))
      (node (ref "OK5") (pin "10") (pinfunction "VO2_10") (pintype "output"))
      (node (ref "R47") (pin "2") (pinfunction "2_2") (pintype "passive"))
    )
    (net (code "56") (name "Net-(IC5A-RO)") (class "Default")
      (node (ref "IC5") (pin "1") (pinfunction "RO_1") (pintype "output"))
      (node (ref "OK5") (pin "13") (pinfunction "C3_13") (pintype "passive"))
    )
    (net (code "57") (name "Net-(IC6A-A)") (class "Default")
      (node (ref "IC6") (pin "6") (pinfunction "A_6") (pintype "passive"))
      (node (ref "R73") (pin "2") (pinfunction "2_2") (pintype "passive"))
      (node (ref "R74") (pin "1") (pinfunction "1_1") (pintype "passive"))
      (node (ref "R92") (pin "1") (pinfunction "1_1") (pintype "passive"))
    )
    (net (code "58") (name "Net-(IC6A-B)") (class "Default")
      (node (ref "IC6") (pin "7") (pinfunction "B_7") (pintype "passive"))
      (node (ref "R72") (pin "2") (pinfunction "2_2") (pintype "passive"))
      (node (ref "R73") (pin "1") (pinfunction "1_1") (pintype "passive"))
      (node (ref "R91") (pin "1") (pinfunction "1_1") (pintype "passive"))
    )
    (net (code "59") (name "Net-(IC6A-DE)") (class "Default")
      (node (ref "IC6") (pin "2") (pinfunction "RE/_2") (pintype "input"))
      (node (ref "IC6") (pin "3") (pinfunction "DE_3") (pintype "input"))
      (node (ref "OK6") (pin "11") (pinfunction "VO1_11") (pintype "output"))
      (node (ref "R49") (pin "2") (pinfunction "2_2") (pintype "passive"))
    )
    (net (code "60") (name "Net-(IC6A-DI)") (class "Default")
      (node (ref "IC6") (pin "4") (pinfunction "DI_4") (pintype "input"))
      (node (ref "OK6") (pin "10") (pinfunction "VO2_10") (pintype "output"))
      (node (ref "R50") (pin "2") (pinfunction "2_2") (pintype "passive"))
    )
    (net (code "61") (name "Net-(IC6A-RO)") (class "Default")
      (node (ref "IC6") (pin "1") (pinfunction "RO_1") (pintype "output"))
      (node (ref "OK6") (pin "13") (pinfunction "C3_13") (pintype "passive"))
    )
    (net (code "62") (name "Net-(IC7A-A)") (class "Default")
      (node (ref "IC7") (pin "6") (pinfunction "A_6") (pintype "passive"))
      (node (ref "R76") (pin "2") (pinfunction "2_2") (pintype "passive"))
      (node (ref "R77") (pin "1") (pinfunction "1_1") (pintype "passive"))
      (node (ref "R94") (pin "1") (pinfunction "1_1") (pintype "passive"))
    )
    (net (code "63") (name "Net-(IC7A-B)") (class "Default")
      (node (ref "IC7") (pin "7") (pinfunction "B_7") (pintype "passive"))
      (node (ref "R75") (pin "2") (pinfunction "2_2") (pintype "passive"))
      (node (ref "R76") (pin "1") (pinfunction "1_1") (pintype "passive"))
      (node (ref "R93") (pin "1") (pinfunction "1_1") (pintype "passive"))
    )
    (net (code "64") (name "Net-(IC7A-DE)") (class "Default")
      (node (ref "IC7") (pin "2") (pinfunction "RE/_2") (pintype "input"))
      (node (ref "IC7") (pin "3") (pinfunction "DE_3") (pintype "input"))
      (node (ref "OK7") (pin "11") (pinfunction "VO1_11") (pintype "output"))
      (node (ref "R52") (pin "2") (pinfunction "2_2") (pintype "passive"))
    )
    (net (code "65") (name "Net-(IC7A-DI)") (class "Default")
      (node (ref "IC7") (pin "4") (pinfunction "DI_4") (pintype "input"))
      (node (ref "OK7") (pin "10") (pinfunction "VO2_10") (pintype "output"))
      (node (ref "R53") (pin "2") (pinfunction "2_2") (pintype "passive"))
    )
    (net (code "66") (name "Net-(IC7A-RO)") (class "Default")
      (node (ref "IC7") (pin "1") (pinfunction "RO_1") (pintype "output"))
      (node (ref "OK7") (pin "13") (pinfunction "C3_13") (pintype "passive"))
    )
    (net (code "67") (name "Net-(IC8A-A)") (class "Default")
      (node (ref "IC8") (pin "6") (pinfunction "A_6") (pintype "passive"))
      (node (ref "R79") (pin "2") (pinfunction "2_2") (pintype "passive"))
      (node (ref "R80") (pin "1") (pinfunction "1_1") (pintype "passive"))
      (node (ref "R96") (pin "1") (pinfunction "1_1") (pintype "passive"))
    )
    (net (code "68") (name "Net-(IC8A-B)") (class "Default")
      (node (ref "IC8") (pin "7") (pinfunction "B_7") (pintype "passive"))
      (node (ref "R78") (pin "2") (pinfunction "2_2") (pintype "passive"))
      (node (ref "R79") (pin "1") (pinfunction "1_1") (pintype "passive"))
      (node (ref "R95") (pin "1") (pinfunction "1_1") (pintype "passive"))
    )
    (net (code "69") (name "Net-(IC8A-DE)") (class "Default")
      (node (ref "IC8") (pin "2") (pinfunction "RE/_2") (pintype "input"))
      (node (ref "IC8") (pin "3") (pinfunction "DE_3") (pintype "input"))
      (node (ref "OK8") (pin "11") (pinfunction "VO1_11") (pintype "output"))
      (node (ref "R55") (pin "2") (pinfunction "2_2") (pintype "passive"))
    )
    (net (code "70") (name "Net-(IC8A-DI)") (class "Default")
      (node (ref "IC8") (pin "4") (pinfunction "DI_4") (pintype "input"))
      (node (ref "OK8") (pin "10") (pinfunction "VO2_10") (pintype "output"))
      (node (ref "R56") (pin "2") (pinfunction "2_2") (pintype "passive"))
    )
    (net (code "71") (name "Net-(IC8A-RO)") (class "Default")
      (node (ref "IC8") (pin "1") (pinfunction "RO_1") (pintype "output"))
      (node (ref "OK8") (pin "13") (pinfunction "C3_13") (pintype "passive"))
    )
    (net (code "72") (name "Net-(OK1-A1)") (class "Default")
      (node (ref "OK1") (pin "5") (pinfunction "A1_5") (pintype "passive"))
      (node (ref "R10") (pin "1") (pinfunction "1_1") (pintype "passive"))
    )
    (net (code "73") (name "Net-(OK1-A2)") (class "Default")
      (node (ref "OK1") (pin "7") (pinfunction "A2_7") (pintype "passive"))
      (node (ref "R11") (pin "1") (pinfunction "1_1") (pintype "passive"))
    )
    (net (code "74") (name "Net-(OK1-A3)") (class "Default")
      (node (ref "OK1") (pin "14") (pinfunction "A3_14") (pintype "passive"))
      (node (ref "R33") (pin "2") (pinfunction "2_2") (pintype "passive"))
    )
    (net (code "75") (name "Net-(OK2-A1)") (class "Default")
      (node (ref "OK2") (pin "5") (pinfunction "A1_5") (pintype "passive"))
      (node (ref "R13") (pin "1") (pinfunction "1_1") (pintype "passive"))
    )
    (net (code "76") (name "Net-(OK2-A2)") (class "Default")
      (node (ref "OK2") (pin "7") (pinfunction "A2_7") (pintype "passive"))
      (node (ref "R14") (pin "1") (pinfunction "1_1") (pintype "passive"))
    )
    (net (code "77") (name "Net-(OK2-A3)") (class "Default")
      (node (ref "OK2") (pin "14") (pinfunction "A3_14") (pintype "passive"))
      (node (ref "R36") (pin "2") (pinfunction "2_2") (pintype "passive"))
    )
    (net (code "78") (name "Net-(OK3-A1)") (class "Default")
      (node (ref "OK3") (pin "5") (pinfunction "A1_5") (pintype "passive"))
      (node (ref "R16") (pin "1") (pinfunction "1_1") (pintype "passive"))
    )
    (net (code "79") (name "Net-(OK3-A2)") (class "Default")
      (node (ref "OK3") (pin "7") (pinfunction "A2_7") (pintype "passive"))
      (node (ref "R17") (pin "1") (pinfunction "1_1") (pintype "passive"))
    )
    (net (code "80") (name "Net-(OK3-A3)") (class "Default")
      (node (ref "OK3") (pin "14") (pinfunction "A3_14") (pintype "passive"))
      (node (ref "R39") (pin "2") (pinfunction "2_2") (pintype "passive"))
    )
    (net (code "81") (name "Net-(OK4-A1)") (class "Default")
      (node (ref "OK4") (pin "5") (pinfunction "A1_5") (pintype "passive"))
      (node (ref "R19") (pin "1") (pinfunction "1_1") (pintype "passive"))
    )
    (net (code "82") (name "Net-(OK4-A2)") (class "Default")
      (node (ref "OK4") (pin "7") (pinfunction "A2_7") (pintype "passive"))
      (node (ref "R20") (pin "1") (pinfunction "1_1") (pintype "passive"))
    )
    (net (code "83") (name "Net-(OK4-A3)") (class "Default")
      (node (ref "OK4") (pin "14") (pinfunction "A3_14") (pintype "passive"))
      (node (ref "R42") (pin "2") (pinfunction "2_2") (pintype "passive"))
    )
    (net (code "84") (name "Net-(OK5-A1)") (class "Default")
      (node (ref "OK5") (pin "5") (pinfunction "A1_5") (pintype "passive"))
      (node (ref "R22") (pin "1") (pinfunction "1_1") (pintype "passive"))
    )
    (net (code "85") (name "Net-(OK5-A2)") (class "Default")
      (node (ref "OK5") (pin "7") (pinfunction "A2_7") (pintype "passive"))
      (node (ref "R23") (pin "1") (pinfunction "1_1") (pintype "passive"))
    )
    (net (code "86") (name "Net-(OK5-A3)") (class "Default")
      (node (ref "OK5") (pin "14") (pinfunction "A3_14") (pintype "passive"))
      (node (ref "R45") (pin "2") (pinfunction "2_2") (pintype "passive"))
    )
    (net (code "87") (name "Net-(OK6-A1)") (class "Default")
      (node (ref "OK6") (pin "5") (pinfunction "A1_5") (pintype "passive"))
      (node (ref "R25") (pin "1") (pinfunction "1_1") (pintype "passive"))
    )
    (net (code "88") (name "Net-(OK6-A2)") (class "Default")
      (node (ref "OK6") (pin "7") (pinfunction "A2_7") (pintype "passive"))
      (node (ref "R26") (pin "1") (pinfunction "1_1") (pintype "passive"))
    )
    (net (code "89") (name "Net-(OK6-A3)") (class "Default")
      (node (ref "OK6") (pin "14") (pinfunction "A3_14") (pintype "passive"))
      (node (ref "R48") (pin "2") (pinfunction "2_2") (pintype "passive"))
    )
    (net (code "90") (name "Net-(OK7-A1)") (class "Default")
      (node (ref "OK7") (pin "5") (pinfunction "A1_5") (pintype "passive"))
      (node (ref "R28") (pin "1") (pinfunction "1_1") (pintype "passive"))
    )
    (net (code "91") (name "Net-(OK7-A2)") (class "Default")
      (node (ref "OK7") (pin "7") (pinfunction "A2_7") (pintype "passive"))
      (node (ref "R29") (pin "1") (pinfunction "1_1") (pintype "passive"))
    )
    (net (code "92") (name "Net-(OK7-A3)") (class "Default")
      (node (ref "OK7") (pin "14") (pinfunction "A3_14") (pintype "passive"))
      (node (ref "R51") (pin "2") (pinfunction "2_2") (pintype "passive"))
    )
    (net (code "93") (name "Net-(OK8-A1)") (class "Default")
      (node (ref "OK8") (pin "5") (pinfunction "A1_5") (pintype "passive"))
      (node (ref "R31") (pin "1") (pinfunction "1_1") (pintype "passive"))
    )
    (net (code "94") (name "Net-(OK8-A2)") (class "Default")
      (node (ref "OK8") (pin "7") (pinfunction "A2_7") (pintype "passive"))
      (node (ref "R32") (pin "1") (pinfunction "1_1") (pintype "passive"))
    )
    (net (code "95") (name "Net-(OK8-A3)") (class "Default")
      (node (ref "OK8") (pin "14") (pinfunction "A3_14") (pintype "passive"))
      (node (ref "R54") (pin "2") (pinfunction "2_2") (pintype "passive"))
    )
    (net (code "96") (name "Net-(X1B-1)") (class "Default")
      (node (ref "D9") (pin "1") (pinfunction "1_1") (pintype "passive"))
      (node (ref "R81") (pin "2") (pinfunction "2_2") (pintype "passive"))
      (node (ref "X1") (pin "2") (pinfunction "1_2") (pintype "passive"))
    )
    (net (code "97") (name "Net-(X1C-1)") (class "Default")
      (node (ref "D9") (pin "2") (pinfunction "2_2") (pintype "passive"))
      (node (ref "R82") (pin "2") (pinfunction "2_2") (pintype "passive"))
      (node (ref "X1") (pin "3") (pinfunction "1_3") (pintype "passive"))
    )
    (net (code "98") (name "Net-(X2B-1)") (class "Default")
      (node (ref "D10") (pin "1") (pinfunction "1_1") (pintype "passive"))
      (node (ref "R83") (pin "2") (pinfunction "2_2") (pintype "passive"))
      (node (ref "X2") (pin "2") (pinfunction "1_2") (pintype "passive"))
    )
    (net (code "99") (name "Net-(X2C-1)") (class "Default")
      (node (ref "D10") (pin "2") (pinfunction "2_2") (pintype "passive"))
      (node (ref "R84") (pin "2") (pinfunction "2_2") (pintype "passive"))
      (node (ref "X2") (pin "3") (pinfunction "1_3") (pintype "passive"))
    )
    (net (code "100") (name "Net-(X3B-1)") (class "Default")
      (node (ref "D11") (pin "1") (pinfunction "1_1") (pintype "passive"))
      (node (ref "R85") (pin "2") (pinfunction "2_2") (pintype "passive"))
      (node (ref "X3") (pin "2") (pinfunction "1_2") (pintype "passive"))
    )
    (net (code "101") (name "Net-(X3C-1)") (class "Default")
      (node (ref "D11") (pin "2") (pinfunction "2_2") (pintype "passive"))
      (node (ref "R86") (pin "2") (pinfunction "2_2") (pintype "passive"))
      (node (ref "X3") (pin "3") (pinfunction "1_3") (pintype "passive"))
    )
    (net (code "102") (name "Net-(X4B-1)") (class "Default")
      (node (ref "D12") (pin "1") (pinfunction "1_1") (pintype "passive"))
      (node (ref "R87") (pin "2") (pinfunction "2_2") (pintype "passive"))
      (node (ref "X4") (pin "2") (pinfunction "1_2") (pintype "passive"))
    )
    (net (code "103") (name "Net-(X4C-1)") (class "Default")
      (node (ref "D12") (pin "2") (pinfunction "2_2") (pintype "passive"))
      (node (ref "R88") (pin "2") (pinfunction "2_2") (pintype "passive"))
      (node (ref "X4") (pin "3") (pinfunction "1_3") (pintype "passive"))
    )
    (net (code "104") (name "Net-(X5B-1)") (class "Default")
      (node (ref "D13") (pin "1") (pinfunction "1_1") (pintype "passive"))
      (node (ref "R89") (pin "2") (pinfunction "2_2") (pintype "passive"))
      (node (ref "X5") (pin "2") (pinfunction "1_2") (pintype "passive"))
    )
    (net (code "105") (name "Net-(X5C-1)") (class "Default")
      (node (ref "D13") (pin "2") (pinfunction "2_2") (pintype "passive"))
      (node (ref "R90") (pin "2") (pinfunction "2_2") (pintype "passive"))
      (node (ref "X5") (pin "3") (pinfunction "1_3") (pintype "passive"))
    )
    (net (code "106") (name "Net-(X6B-1)") (class "Default")
      (node (ref "D14") (pin "1") (pinfunction "1_1") (pintype "passive"))
      (node (ref "R91") (pin "2") (pinfunction "2_2") (pintype "passive"))
      (node (ref "X6") (pin "2") (pinfunction "1_2") (pintype "passive"))
    )
    (net (code "107") (name "Net-(X6C-1)") (class "Default")
      (node (ref "D14") (pin "2") (pinfunction "2_2") (pintype "passive"))
      (node (ref "R92") (pin "2") (pinfunction "2_2") (pintype "passive"))
      (node (ref "X6") (pin "3") (pinfunction "1_3") (pintype "passive"))
    )
    (net (code "108") (name "Net-(X7B-1)") (class "Default")
      (node (ref "D15") (pin "1") (pinfunction "1_1") (pintype "passive"))
      (node (ref "R93") (pin "2") (pinfunction "2_2") (pintype "passive"))
      (node (ref "X7") (pin "2") (pinfunction "1_2") (pintype "passive"))
    )
    (net (code "109") (name "Net-(X7C-1)") (class "Default")
      (node (ref "D15") (pin "2") (pinfunction "2_2") (pintype "passive"))
      (node (ref "R94") (pin "2") (pinfunction "2_2") (pintype "passive"))
      (node (ref "X7") (pin "3") (pinfunction "1_3") (pintype "passive"))
    )
    (net (code "110") (name "Net-(X8B-1)") (class "Default")
      (node (ref "D16") (pin "1") (pinfunction "1_1") (pintype "passive"))
      (node (ref "R95") (pin "2") (pinfunction "2_2") (pintype "passive"))
      (node (ref "X8") (pin "2") (pinfunction "1_2") (pintype "passive"))
    )
    (net (code "111") (name "Net-(X8C-1)") (class "Default")
      (node (ref "D16") (pin "2") (pinfunction "2_2") (pintype "passive"))
      (node (ref "R96") (pin "2") (pinfunction "2_2") (pintype "passive"))
      (node (ref "X8") (pin "3") (pinfunction "1_3") (pintype "passive"))
    )
    (net (code "112") (name "U0RX") (class "Default")
      (node (ref "J5") (pin "5") (pinfunction "5_5") (pintype "passive"))
      (node (ref "OK1") (pin "3") (pinfunction "V03_3") (pintype "output"))
      (node (ref "OK2") (pin "3") (pinfunction "V03_3") (pintype "output"))
      (node (ref "OK3") (pin "3") (pinfunction "V03_3") (pintype "output"))
      (node (ref "OK4") (pin "3") (pinfunction "V03_3") (pintype "output"))
      (node (ref "OK5") (pin "3") (pinfunction "V03_3") (pintype "output"))
      (node (ref "OK6") (pin "3") (pinfunction "V03_3") (pintype "output"))
      (node (ref "OK7") (pin "3") (pinfunction "V03_3") (pintype "output"))
      (node (ref "OK8") (pin "3") (pinfunction "V03_3") (pintype "output"))
      (node (ref "R12") (pin "2") (pinfunction "2_2") (pintype "passive"))
      (node (ref "R15") (pin "2") (pinfunction "2_2") (pintype "passive"))
      (node (ref "R18") (pin "2") (pinfunction "2_2") (pintype "passive"))
      (node (ref "R21") (pin "2") (pinfunction "2_2") (pintype "passive"))
      (node (ref "R24") (pin "2") (pinfunction "2_2") (pintype "passive"))
      (node (ref "R27") (pin "2") (pinfunction "2_2") (pintype "passive"))
      (node (ref "R30") (pin "2") (pinfunction "2_2") (pintype "passive"))
      (node (ref "R9") (pin "2") (pinfunction "2_2") (pintype "passive"))
    )
    (net (code "113") (name "U0SEL") (class "Default")
      (node (ref "OK1") (pin "6") (pinfunction "C1_6") (pintype "passive"))
      (node (ref "OK2") (pin "6") (pinfunction "C1_6") (pintype "passive"))
      (node (ref "OK3") (pin "6") (pinfunction "C1_6") (pintype "passive"))
      (node (ref "OK4") (pin "6") (pinfunction "C1_6") (pintype "passive"))
      (node (ref "OK5") (pin "6") (pinfunction "C1_6") (pintype "passive"))
      (node (ref "OK6") (pin "6") (pinfunction "C1_6") (pintype "passive"))
      (node (ref "OK7") (pin "6") (pinfunction "C1_6") (pintype "passive"))
      (node (ref "OK8") (pin "6") (pinfunction "C1_6") (pintype "passive"))
    )
    (net (code "114") (name "U0TX") (class "Default")
      (node (ref "J5") (pin "6") (pinfunction "6_6") (pintype "passive"))
      (node (ref "J8") (pin "3") (pinfunction "3_3") (pintype "passive"))
      (node (ref "OK1") (pin "8") (pinfunction "C2_8") (pintype "passive"))
      (node (ref "OK2") (pin "8") (pinfunction "C2_8") (pintype "passive"))
      (node (ref "OK3") (pin "8") (pinfunction "C2_8") (pintype "passive"))
      (node (ref "OK4") (pin "8") (pinfunction "C2_8") (pintype "passive"))
      (node (ref "OK5") (pin "8") (pinfunction "C2_8") (pintype "passive"))
      (node (ref "OK6") (pin "8") (pinfunction "C2_8") (pintype "passive"))
      (node (ref "OK7") (pin "8") (pinfunction "C2_8") (pintype "passive"))
      (node (ref "OK8") (pin "8") (pinfunction "C2_8") (pintype "passive"))
      (node (ref "X11") (pin "9") (pinfunction "1_9") (pintype "passive"))
    )
    (net (code "115") (name "U1TX") (class "Default")
      (node (ref "J10") (pin "2") (pinfunction "2_2") (pintype "passive"))
      (node (ref "X11") (pin "8") (pinfunction "1_8") (pintype "passive"))
    )
    (net (code "116") (name "U2RX") (class "Default")
      (node (ref "J4") (pin "8") (pinfunction "8_8") (pintype "passive"))
    )
    (net (code "117") (name "U2TX") (class "Default")
      (node (ref "J14") (pin "4") (pinfunction "4_4") (pintype "passive"))
      (node (ref "J18") (pin "5") (pinfunction "5_5") (pintype "passive"))
      (node (ref "J19") (pin "7") (pinfunction "7_7") (pintype "passive"))
      (node (ref "X11") (pin "7") (pinfunction "1_7") (pintype "passive"))
    )
    (net (code "118") (name "U3RX") (class "Default")
      (node (ref "J6") (pin "9") (pinfunction "9_9") (pintype "passive"))
    )
    (net (code "119") (name "U3TX") (class "Default")
      (node (ref "J22") (pin "6") (pinfunction "6_6") (pintype "passive"))
      (node (ref "J6") (pin "10") (pinfunction "10_10") (pintype "passive"))
      (node (ref "J8") (pin "7") (pinfunction "7_7") (pintype "passive"))
      (node (ref "X11") (pin "6") (pinfunction "1_6") (pintype "passive"))
    )
    (net (code "120") (name "U4RX") (class "Default")
      (node (ref "J6") (pin "5") (pinfunction "5_5") (pintype "passive"))
    )
    (net (code "121") (name "U4TX") (class "Default")
      (node (ref "J20") (pin "7") (pinfunction "7_7") (pintype "passive"))
      (node (ref "J22") (pin "4") (pinfunction "4_4") (pintype "passive"))
      (node (ref "J6") (pin "6") (pinfunction "6_6") (pintype "passive"))
      (node (ref "X11") (pin "5") (pinfunction "1_5") (pintype "passive"))
    )
    (net (code "122") (name "U5RX") (class "Default")
      (node (ref "J3") (pin "5") (pinfunction "5_5") (pintype "passive"))
    )
    (net (code "123") (name "U5TX") (class "Default")
      (node (ref "J19") (pin "2") (pinfunction "2_2") (pintype "passive"))
      (node (ref "J3") (pin "8") (pinfunction "8_8") (pintype "passive"))
      (node (ref "X11") (pin "4") (pinfunction "1_4") (pintype "passive"))
    )
    (net (code "124") (name "U6RX") (class "Default")
      (node (ref "J5") (pin "3") (pinfunction "3_3") (pintype "passive"))
    )
    (net (code "125") (name "U6TX") (class "Default")
      (node (ref "J16") (pin "7") (pinfunction "7_7") (pintype "passive"))
      (node (ref "J5") (pin "4") (pinfunction "4_4") (pintype "passive"))
      (node (ref "X11") (pin "3") (pinfunction "1_3") (pintype "passive"))
    )
    (net (code "126") (name "U7RX") (class "Default")
      (node (ref "J3") (pin "3") (pinfunction "3_3") (pintype "passive"))
    )
    (net (code "127") (name "U7TX") (class "Default")
      (node (ref "J19") (pin "4") (pinfunction "4_4") (pintype "passive"))
      (node (ref "J3") (pin "4") (pinfunction "4_4") (pintype "passive"))
      (node (ref "X11") (pin "2") (pinfunction "1_2") (pintype "passive"))
    )
    (net (code "128") (name "VIN-1") (class "Default")
      (node (ref "C1") (pin "+") (pinfunction "+_+") (pintype "passive"))
      (node (ref "C17") (pin "1") (pinfunction "1_1") (pintype "passive"))
      (node (ref "C9") (pin "1") (pinfunction "1_1") (pintype "passive"))
      (node (ref "D1") (pin "A") (pinfunction "A_A") (pintype "passive"))
      (node (ref "DC1") (pin "2") (pinfunction "+VIN_2") (pintype "passive"))
      (node (ref "F1") (pin "2") (pinfunction "2_2") (pintype "bidirectional"))
      (node (ref "OK1") (pin "4") (pinfunction "VDD1_4") (pintype "power_in"))
      (node (ref "R10") (pin "2") (pinfunction "2_2") (pintype "passive"))
      (node (ref "R11") (pin "2") (pinfunction "2_2") (pintype "passive"))
      (node (ref "R9") (pin "1") (pinfunction "1_1") (pintype "passive"))
      (node (ref "U1") (pin "C") (pinfunction "C_C") (pintype "passive"))
    )
    (net (code "129") (name "VIN-2") (class "Default")
      (node (ref "C10") (pin "1") (pinfunction "1_1") (pintype "passive"))
      (node (ref "C18") (pin "1") (pinfunction "1_1") (pintype "passive"))
      (node (ref "C2") (pin "+") (pinfunction "+_+") (pintype "passive"))
      (node (ref "D2") (pin "A") (pinfunction "A_A") (pintype "passive"))
      (node (ref "DC2") (pin "2") (pinfunction "+VIN_2") (pintype "passive"))
      (node (ref "F2") (pin "2") (pinfunction "2_2") (pintype "bidirectional"))
      (node (ref "OK2") (pin "4") (pinfunction "VDD1_4") (pintype "power_in"))
      (node (ref "R12") (pin "1") (pinfunction "1_1") (pintype "passive"))
      (node (ref "R13") (pin "2") (pinfunction "2_2") (pintype "passive"))
      (node (ref "R14") (pin "2") (pinfunction "2_2") (pintype "passive"))
      (node (ref "U2") (pin "C") (pinfunction "C_C") (pintype "passive"))
    )
    (net (code "130") (name "VIN-3") (class "Default")
      (node (ref "C11") (pin "1") (pinfunction "1_1") (pintype "passive"))
      (node (ref "C19") (pin "1") (pinfunction "1_1") (pintype "passive"))
      (node (ref "C3") (pin "+") (pinfunction "+_+") (pintype "passive"))
      (node (ref "D3") (pin "A") (pinfunction "A_A") (pintype "passive"))
      (node (ref "DC3") (pin "2") (pinfunction "+VIN_2") (pintype "passive"))
      (node (ref "F3") (pin "2") (pinfunction "2_2") (pintype "bidirectional"))
      (node (ref "OK3") (pin "4") (pinfunction "VDD1_4") (pintype "power_in"))
      (node (ref "R15") (pin "1") (pinfunction "1_1") (pintype "passive"))
      (node (ref "R16") (pin "2") (pinfunction "2_2") (pintype "passive"))
      (node (ref "R17") (pin "2") (pinfunction "2_2") (pintype "passive"))
      (node (ref "U3") (pin "C") (pinfunction "C_C") (pintype "passive"))
    )
    (net (code "131") (name "VIN-4") (class "Default")
      (node (ref "C12") (pin "1") (pinfunction "1_1") (pintype "passive"))
      (node (ref "C20") (pin "1") (pinfunction "1_1") (pintype "passive"))
      (node (ref "C4") (pin "+") (pinfunction "+_+") (pintype "passive"))
      (node (ref "D4") (pin "A") (pinfunction "A_A") (pintype "passive"))
      (node (ref "DC4") (pin "2") (pinfunction "+VIN_2") (pintype "passive"))
      (node (ref "F4") (pin "2") (pinfunction "2_2") (pintype "bidirectional"))
      (node (ref "OK4") (pin "4") (pinfunction "VDD1_4") (pintype "power_in"))
      (node (ref "R18") (pin "1") (pinfunction "1_1") (pintype "passive"))
      (node (ref "R19") (pin "2") (pinfunction "2_2") (pintype "passive"))
      (node (ref "R20") (pin "2") (pinfunction "2_2") (pintype "passive"))
      (node (ref "U4") (pin "C") (pinfunction "C_C") (pintype "passive"))
    )
    (net (code "132") (name "VIN-5") (class "Default")
      (node (ref "C13") (pin "1") (pinfunction "1_1") (pintype "passive"))
      (node (ref "C21") (pin "1") (pinfunction "1_1") (pintype "passive"))
      (node (ref "C5") (pin "+") (pinfunction "+_+") (pintype "passive"))
      (node (ref "D5") (pin "A") (pinfunction "A_A") (pintype "passive"))
      (node (ref "DC5") (pin "2") (pinfunction "+VIN_2") (pintype "passive"))
      (node (ref "F5") (pin "2") (pinfunction "2_2") (pintype "bidirectional"))
      (node (ref "OK5") (pin "4") (pinfunction "VDD1_4") (pintype "power_in"))
      (node (ref "R21") (pin "1") (pinfunction "1_1") (pintype "passive"))
      (node (ref "R22") (pin "2") (pinfunction "2_2") (pintype "passive"))
      (node (ref "R23") (pin "2") (pinfunction "2_2") (pintype "passive"))
      (node (ref "U5") (pin "C") (pinfunction "C_C") (pintype "passive"))
    )
    (net (code "133") (name "VIN-6") (class "Default")
      (node (ref "C14") (pin "1") (pinfunction "1_1") (pintype "passive"))
      (node (ref "C22") (pin "1") (pinfunction "1_1") (pintype "passive"))
      (node (ref "C6") (pin "+") (pinfunction "+_+") (pintype "passive"))
      (node (ref "D6") (pin "A") (pinfunction "A_A") (pintype "passive"))
      (node (ref "DC6") (pin "2") (pinfunction "+VIN_2") (pintype "passive"))
      (node (ref "F6") (pin "2") (pinfunction "2_2") (pintype "bidirectional"))
      (node (ref "OK6") (pin "4") (pinfunction "VDD1_4") (pintype "power_in"))
      (node (ref "R24") (pin "1") (pinfunction "1_1") (pintype "passive"))
      (node (ref "R25") (pin "2") (pinfunction "2_2") (pintype "passive"))
      (node (ref "R26") (pin "2") (pinfunction "2_2") (pintype "passive"))
      (node (ref "U6") (pin "C") (pinfunction "C_C") (pintype "passive"))
    )
    (net (code "134") (name "VIN-7") (class "Default")
      (node (ref "C15") (pin "1") (pinfunction "1_1") (pintype "passive"))
      (node (ref "C23") (pin "1") (pinfunction "1_1") (pintype "passive"))
      (node (ref "C7") (pin "+") (pinfunction "+_+") (pintype "passive"))
      (node (ref "D7") (pin "A") (pinfunction "A_A") (pintype "passive"))
      (node (ref "DC7") (pin "2") (pinfunction "+VIN_2") (pintype "passive"))
      (node (ref "F7") (pin "2") (pinfunction "2_2") (pintype "bidirectional"))
      (node (ref "OK7") (pin "4") (pinfunction "VDD1_4") (pintype "power_in"))
      (node (ref "R27") (pin "1") (pinfunction "1_1") (pintype "passive"))
      (node (ref "R28") (pin "2") (pinfunction "2_2") (pintype "passive"))
      (node (ref "R29") (pin "2") (pinfunction "2_2") (pintype "passive"))
      (node (ref "U7") (pin "C") (pinfunction "C_C") (pintype "passive"))
    )
    (net (code "135") (name "VIN-8") (class "Default")
      (node (ref "C16") (pin "1") (pinfunction "1_1") (pintype "passive"))
      (node (ref "C24") (pin "1") (pinfunction "1_1") (pintype "passive"))
      (node (ref "C8") (pin "+") (pinfunction "+_+") (pintype "passive"))
      (node (ref "D8") (pin "A") (pinfunction "A_A") (pintype "passive"))
      (node (ref "DC8") (pin "2") (pinfunction "+VIN_2") (pintype "passive"))
      (node (ref "F8") (pin "2") (pinfunction "2_2") (pintype "bidirectional"))
      (node (ref "OK8") (pin "4") (pinfunction "VDD1_4") (pintype "power_in"))
      (node (ref "R30") (pin "1") (pinfunction "1_1") (pintype "passive"))
      (node (ref "R31") (pin "2") (pinfunction "2_2") (pintype "passive"))
      (node (ref "R32") (pin "2") (pinfunction "2_2") (pintype "passive"))
      (node (ref "U8") (pin "C") (pinfunction "C_C") (pintype "passive"))
    )
    (net (code "136") (name "unconnected-(DC9-ON{slash}OFF-Pad2)") (class "Default")
      (node (ref "DC9") (pin "2") (pinfunction "ON/OFF_2") (pintype "bidirectional"))
    )
    (net (code "137") (name "unconnected-(DC9-TRIM-Pad5)") (class "Default")
      (node (ref "DC9") (pin "5") (pinfunction "TRIM_5") (pintype "bidirectional"))
    )
    (net (code "138") (name "unconnected-(J1-Pad1)") (class "Default")
      (node (ref "J1") (pin "1") (pinfunction "1_1") (pintype "passive"))
    )
    (net (code "139") (name "unconnected-(J1-Pad2)") (class "Default")
      (node (ref "J1") (pin "2") (pinfunction "2_2") (pintype "passive"))
    )
    (net (code "140") (name "unconnected-(J1-Pad3)") (class "Default")
      (node (ref "J1") (pin "3") (pinfunction "3_3") (pintype "passive"))
    )
    (net (code "141") (name "unconnected-(J1-Pad4)") (class "Default")
      (node (ref "J1") (pin "4") (pinfunction "4_4") (pintype "passive"))
    )
    (net (code "142") (name "unconnected-(J1-Pad5)") (class "Default")
      (node (ref "J1") (pin "5") (pinfunction "5_5") (pintype "passive"))
    )
    (net (code "143") (name "unconnected-(J1-Pad6)") (class "Default")
      (node (ref "J1") (pin "6") (pinfunction "6_6") (pintype "passive"))
    )
    (net (code "144") (name "unconnected-(J2-Pad1)") (class "Default")
      (node (ref "J2") (pin "1") (pinfunction "1_1") (pintype "passive"))
    )
    (net (code "145") (name "unconnected-(J2-Pad2)") (class "Default")
      (node (ref "J2") (pin "2") (pinfunction "2_2") (pintype "passive"))
    )
    (net (code "146") (name "unconnected-(J2-Pad3)") (class "Default")
      (node (ref "J2") (pin "3") (pinfunction "3_3") (pintype "passive"))
    )
    (net (code "147") (name "unconnected-(J2-Pad4)") (class "Default")
      (node (ref "J2") (pin "4") (pinfunction "4_4") (pintype "passive"))
    )
    (net (code "148") (name "unconnected-(J2-Pad5)") (class "Default")
      (node (ref "J2") (pin "5") (pinfunction "5_5") (pintype "passive"))
    )
    (net (code "149") (name "unconnected-(J3-Pad2)") (class "Default")
      (node (ref "J3") (pin "2") (pinfunction "2_2") (pintype "passive"))
    )
    (net (code "150") (name "unconnected-(J3-Pad6)") (class "Default")
      (node (ref "J3") (pin "6") (pinfunction "6_6") (pintype "passive"))
    )
    (net (code "151") (name "unconnected-(J3-Pad7)") (class "Default")
      (node (ref "J3") (pin "7") (pinfunction "7_7") (pintype "passive"))
    )
    (net (code "152") (name "unconnected-(J3-Pad9)") (class "Default")
      (node (ref "J3") (pin "9") (pinfunction "9_9") (pintype "passive"))
    )
    (net (code "153") (name "unconnected-(J3-Pad10)") (class "Default")
      (node (ref "J3") (pin "10") (pinfunction "10_10") (pintype "passive"))
    )
    (net (code "154") (name "unconnected-(J4-Pad3)") (class "Default")
      (node (ref "J4") (pin "3") (pinfunction "3_3") (pintype "passive"))
    )
    (net (code "155") (name "unconnected-(J4-Pad4)") (class "Default")
      (node (ref "J4") (pin "4") (pinfunction "4_4") (pintype "passive"))
    )
    (net (code "156") (name "unconnected-(J4-Pad5)") (class "Default")
      (node (ref "J4") (pin "5") (pinfunction "5_5") (pintype "passive"))
    )
    (net (code "157") (name "unconnected-(J4-Pad6)") (class "Default")
      (node (ref "J4") (pin "6") (pinfunction "6_6") (pintype "passive"))
    )
    (net (code "158") (name "unconnected-(J4-Pad7)") (class "Default")
      (node (ref "J4") (pin "7") (pinfunction "7_7") (pintype "passive"))
    )
    (net (code "159") (name "unconnected-(J4-Pad9)") (class "Default")
      (node (ref "J4") (pin "9") (pinfunction "9_9") (pintype "passive"))
    )
    (net (code "160") (name "unconnected-(J4-Pad10)") (class "Default")
      (node (ref "J4") (pin "10") (pinfunction "10_10") (pintype "passive"))
    )
    (net (code "161") (name "unconnected-(J5-Pad2)") (class "Default")
      (node (ref "J5") (pin "2") (pinfunction "2_2") (pintype "passive"))
    )
    (net (code "162") (name "unconnected-(J5-Pad7)") (class "Default")
      (node (ref "J5") (pin "7") (pinfunction "7_7") (pintype "passive"))
    )
    (net (code "163") (name "unconnected-(J5-Pad8)") (class "Default")
      (node (ref "J5") (pin "8") (pinfunction "8_8") (pintype "passive"))
    )
    (net (code "164") (name "unconnected-(J5-Pad9)") (class "Default")
      (node (ref "J5") (pin "9") (pinfunction "9_9") (pintype "passive"))
    )
    (net (code "165") (name "unconnected-(J5-Pad10)") (class "Default")
      (node (ref "J5") (pin "10") (pinfunction "10_10") (pintype "passive"))
    )
    (net (code "166") (name "unconnected-(J6-Pad3)") (class "Default")
      (node (ref "J6") (pin "3") (pinfunction "3_3") (pintype "passive"))
    )
    (net (code "167") (name "unconnected-(J6-Pad4)") (class "Default")
      (node (ref "J6") (pin "4") (pinfunction "4_4") (pintype "passive"))
    )
    (net (code "168") (name "unconnected-(J6-Pad7)") (class "Default")
      (node (ref "J6") (pin "7") (pinfunction "7_7") (pintype "passive"))
    )
    (net (code "169") (name "unconnected-(J6-Pad8)") (class "Default")
      (node (ref "J6") (pin "8") (pinfunction "8_8") (pintype "passive"))
    )
    (net (code "170") (name "unconnected-(J7-Pad1)") (class "Default")
      (node (ref "J7") (pin "1") (pinfunction "1_1") (pintype "passive"))
    )
    (net (code "171") (name "unconnected-(J7-Pad2)") (class "Default")
      (node (ref "J7") (pin "2") (pinfunction "2_2") (pintype "passive"))
    )
    (net (code "172") (name "unconnected-(J7-Pad3)") (class "Default")
      (node (ref "J7") (pin "3") (pinfunction "3_3") (pintype "passive"))
    )
    (net (code "173") (name "unconnected-(J7-Pad4)") (class "Default")
      (node (ref "J7") (pin "4") (pinfunction "4_4") (pintype "passive"))
    )
    (net (code "174") (name "unconnected-(J7-Pad5)") (class "Default")
      (node (ref "J7") (pin "5") (pinfunction "5_5") (pintype "passive"))
    )
    (net (code "175") (name "unconnected-(J7-Pad6)") (class "Default")
      (node (ref "J7") (pin "6") (pinfunction "6_6") (pintype "passive"))
    )
    (net (code "176") (name "unconnected-(J7-Pad7)") (class "Default")
      (node (ref "J7") (pin "7") (pinfunction "7_7") (pintype "passive"))
    )
    (net (code "177") (name "unconnected-(J8-Pad1)") (class "Default")
      (node (ref "J8") (pin "1") (pinfunction "1_1") (pintype "passive"))
    )
    (net (code "178") (name "unconnected-(J8-Pad2)") (class "Default")
      (node (ref "J8") (pin "2") (pinfunction "2_2") (pintype "passive"))
    )
    (net (code "179") (name "unconnected-(J8-Pad4)") (class "Default")
      (node (ref "J8") (pin "4") (pinfunction "4_4") (pintype "passive"))
    )
    (net (code "180") (name "unconnected-(J8-Pad5)") (class "Default")
      (node (ref "J8") (pin "5") (pinfunction "5_5") (pintype "passive"))
    )
    (net (code "181") (name "unconnected-(J8-Pad6)") (class "Default")
      (node (ref "J8") (pin "6") (pinfunction "6_6") (pintype "passive"))
    )
    (net (code "182") (name "unconnected-(J9-Pad1)") (class "Default")
      (node (ref "J9") (pin "1") (pinfunction "1_1") (pintype "passive"))
    )
    (net (code "183") (name "unconnected-(J9-Pad2)") (class "Default")
      (node (ref "J9") (pin "2") (pinfunction "2_2") (pintype "passive"))
    )
    (net (code "184") (name "unconnected-(J9-Pad4)") (class "Default")
      (node (ref "J9") (pin "4") (pinfunction "4_4") (pintype "passive"))
    )
    (net (code "185") (name "unconnected-(J9-Pad5)") (class "Default")
      (node (ref "J9") (pin "5") (pinfunction "5_5") (pintype "passive"))
    )
    (net (code "186") (name "unconnected-(J9-Pad6)") (class "Default")
      (node (ref "J9") (pin "6") (pinfunction "6_6") (pintype "passive"))
    )
    (net (code "187") (name "unconnected-(J9-Pad7)") (class "Default")
      (node (ref "J9") (pin "7") (pinfunction "7_7") (pintype "passive"))
    )
    (net (code "188") (name "unconnected-(J10-Pad1)") (class "Default")
      (node (ref "J10") (pin "1") (pinfunction "1_1") (pintype "passive"))
    )
    (net (code "189") (name "unconnected-(J10-Pad4)") (class "Default")
      (node (ref "J10") (pin "4") (pinfunction "4_4") (pintype "passive"))
    )
    (net (code "190") (name "unconnected-(J10-Pad5)") (class "Default")
      (node (ref "J10") (pin "5") (pinfunction "5_5") (pintype "passive"))
    )
    (net (code "191") (name "unconnected-(J10-Pad6)") (class "Default")
      (node (ref "J10") (pin "6") (pinfunction "6_6") (pintype "passive"))
    )
    (net (code "192") (name "unconnected-(J10-Pad7)") (class "Default")
      (node (ref "J10") (pin "7") (pinfunction "7_7") (pintype "passive"))
    )
    (net (code "193") (name "unconnected-(J11-Pad1)") (class "Default")
      (node (ref "J11") (pin "1") (pinfunction "1_1") (pintype "passive"))
    )
    (net (code "194") (name "unconnected-(J11-Pad2)") (class "Default")
      (node (ref "J11") (pin "2") (pinfunction "2_2") (pintype "passive"))
    )
    (net (code "195") (name "unconnected-(J11-Pad3)") (class "Default")
      (node (ref "J11") (pin "3") (pinfunction "3_3") (pintype "passive"))
    )
    (net (code "196") (name "unconnected-(J11-Pad4)") (class "Default")
      (node (ref "J11") (pin "4") (pinfunction "4_4") (pintype "passive"))
    )
    (net (code "197") (name "unconnected-(J11-Pad5)") (class "Default")
      (node (ref "J11") (pin "5") (pinfunction "5_5") (pintype "passive"))
    )
    (net (code "198") (name "unconnected-(J11-Pad6)") (class "Default")
      (node (ref "J11") (pin "6") (pinfunction "6_6") (pintype "passive"))
    )
    (net (code "199") (name "unconnected-(J11-Pad7)") (class "Default")
      (node (ref "J11") (pin "7") (pinfunction "7_7") (pintype "passive"))
    )
    (net (code "200") (name "unconnected-(J11-Pad8)") (class "Default")
      (node (ref "J11") (pin "8") (pinfunction "8_8") (pintype "passive"))
    )
    (net (code "201") (name "unconnected-(J11-Pad9)") (class "Default")
      (node (ref "J11") (pin "9") (pinfunction "9_9") (pintype "passive"))
    )
    (net (code "202") (name "unconnected-(J11-Pad10)") (class "Default")
      (node (ref "J11") (pin "10") (pinfunction "10_10") (pintype "passive"))
    )
    (net (code "203") (name "unconnected-(J12-Pad2)") (class "Default")
      (node (ref "J12") (pin "2") (pinfunction "2_2") (pintype "passive"))
    )
    (net (code "204") (name "unconnected-(J12-Pad3)") (class "Default")
      (node (ref "J12") (pin "3") (pinfunction "3_3") (pintype "passive"))
    )
    (net (code "205") (name "unconnected-(J12-Pad4)") (class "Default")
      (node (ref "J12") (pin "4") (pinfunction "4_4") (pintype "passive"))
    )
    (net (code "206") (name "unconnected-(J12-Pad5)") (class "Default")
      (node (ref "J12") (pin "5") (pinfunction "5_5") (pintype "passive"))
    )
    (net (code "207") (name "unconnected-(J12-Pad6)") (class "Default")
      (node (ref "J12") (pin "6") (pinfunction "6_6") (pintype "passive"))
    )
    (net (code "208") (name "unconnected-(J12-Pad7)") (class "Default")
      (node (ref "J12") (pin "7") (pinfunction "7_7") (pintype "passive"))
    )
    (net (code "209") (name "unconnected-(J12-Pad8)") (class "Default")
      (node (ref "J12") (pin "8") (pinfunction "8_8") (pintype "passive"))
    )
    (net (code "210") (name "unconnected-(J12-Pad9)") (class "Default")
      (node (ref "J12") (pin "9") (pinfunction "9_9") (pintype "passive"))
    )
    (net (code "211") (name "unconnected-(J12-Pad10)") (class "Default")
      (node (ref "J12") (pin "10") (pinfunction "10_10") (pintype "passive"))
    )
    (net (code "212") (name "unconnected-(J13-Pad1)") (class "Default")
      (node (ref "J13") (pin "1") (pinfunction "1_1") (pintype "passive"))
    )
    (net (code "213") (name "unconnected-(J13-Pad2)") (class "Default")
      (node (ref "J13") (pin "2") (pinfunction "2_2") (pintype "passive"))
    )
    (net (code "214") (name "unconnected-(J13-Pad3)") (class "Default")
      (node (ref "J13") (pin "3") (pinfunction "3_3") (pintype "passive"))
    )
    (net (code "215") (name "unconnected-(J13-Pad4)") (class "Default")
      (node (ref "J13") (pin "4") (pinfunction "4_4") (pintype "passive"))
    )
    (net (code "216") (name "unconnected-(J13-Pad5)") (class "Default")
      (node (ref "J13") (pin "5") (pinfunction "5_5") (pintype "passive"))
    )
    (net (code "217") (name "unconnected-(J13-Pad6)") (class "Default")
      (node (ref "J13") (pin "6") (pinfunction "6_6") (pintype "passive"))
    )
    (net (code "218") (name "unconnected-(J13-Pad7)") (class "Default")
      (node (ref "J13") (pin "7") (pinfunction "7_7") (pintype "passive"))
    )
    (net (code "219") (name "unconnected-(J13-Pad8)") (class "Default")
      (node (ref "J13") (pin "8") (pinfunction "8_8") (pintype "passive"))
    )
    (net (code "220") (name "unconnected-(J13-Pad9)") (class "Default")
      (node (ref "J13") (pin "9") (pinfunction "9_9") (pintype "passive"))
    )
    (net (code "221") (name "unconnected-(J13-Pad10)") (class "Default")
      (node (ref "J13") (pin "10") (pinfunction "10_10") (pintype "passive"))
    )
    (net (code "222") (name "unconnected-(J14-Pad2)") (class "Default")
      (node (ref "J14") (pin "2") (pinfunction "2_2") (pintype "passive"))
    )
    (net (code "223") (name "unconnected-(J14-Pad3)") (class "Default")
      (node (ref "J14") (pin "3") (pinfunction "3_3") (pintype "passive"))
    )
    (net (code "224") (name "unconnected-(J14-Pad5)") (class "Default")
      (node (ref "J14") (pin "5") (pinfunction "5_5") (pintype "passive"))
    )
    (net (code "225") (name "unconnected-(J14-Pad6)") (class "Default")
      (node (ref "J14") (pin "6") (pinfunction "6_6") (pintype "passive"))
    )
    (net (code "226") (name "unconnected-(J14-Pad7)") (class "Default")
      (node (ref "J14") (pin "7") (pinfunction "7_7") (pintype "passive"))
    )
    (net (code "227") (name "unconnected-(J14-Pad8)") (class "Default")
      (node (ref "J14") (pin "8") (pinfunction "8_8") (pintype "passive"))
    )
    (net (code "228") (name "unconnected-(J14-Pad9)") (class "Default")
      (node (ref "J14") (pin "9") (pinfunction "9_9") (pintype "passive"))
    )
    (net (code "229") (name "unconnected-(J14-Pad10)") (class "Default")
      (node (ref "J14") (pin "10") (pinfunction "10_10") (pintype "passive"))
    )
    (net (code "230") (name "unconnected-(J15-Pad1)") (class "Default")
      (node (ref "J15") (pin "1") (pinfunction "1_1") (pintype "passive"))
    )
    (net (code "231") (name "unconnected-(J15-Pad2)") (class "Default")
      (node (ref "J15") (pin "2") (pinfunction "2_2") (pintype "passive"))
    )
    (net (code "232") (name "unconnected-(J15-Pad3)") (class "Default")
      (node (ref "J15") (pin "3") (pinfunction "3_3") (pintype "passive"))
    )
    (net (code "233") (name "unconnected-(J15-Pad4)") (class "Default")
      (node (ref "J15") (pin "4") (pinfunction "4_4") (pintype "passive"))
    )
    (net (code "234") (name "unconnected-(J15-Pad5)") (class "Default")
      (node (ref "J15") (pin "5") (pinfunction "5_5") (pintype "passive"))
    )
    (net (code "235") (name "unconnected-(J15-Pad6)") (class "Default")
      (node (ref "J15") (pin "6") (pinfunction "6_6") (pintype "passive"))
    )
    (net (code "236") (name "unconnected-(J15-Pad7)") (class "Default")
      (node (ref "J15") (pin "7") (pinfunction "7_7") (pintype "passive"))
    )
    (net (code "237") (name "unconnected-(J16-Pad1)") (class "Default")
      (node (ref "J16") (pin "1") (pinfunction "1_1") (pintype "passive"))
    )
    (net (code "238") (name "unconnected-(J16-Pad2)") (class "Default")
      (node (ref "J16") (pin "2") (pinfunction "2_2") (pintype "passive"))
    )
    (net (code "239") (name "unconnected-(J16-Pad3)") (class "Default")
      (node (ref "J16") (pin "3") (pinfunction "3_3") (pintype "passive"))
    )
    (net (code "240") (name "unconnected-(J16-Pad4)") (class "Default")
      (node (ref "J16") (pin "4") (pinfunction "4_4") (pintype "passive"))
    )
    (net (code "241") (name "unconnected-(J16-Pad5)") (class "Default")
      (node (ref "J16") (pin "5") (pinfunction "5_5") (pintype "passive"))
    )
    (net (code "242") (name "unconnected-(J16-Pad6)") (class "Default")
      (node (ref "J16") (pin "6") (pinfunction "6_6") (pintype "passive"))
    )
    (net (code "243") (name "unconnected-(J17-Pad1)") (class "Default")
      (node (ref "J17") (pin "1") (pinfunction "1_1") (pintype "passive"))
    )
    (net (code "244") (name "unconnected-(J17-Pad2)") (class "Default")
      (node (ref "J17") (pin "2") (pinfunction "2_2") (pintype "passive"))
    )
    (net (code "245") (name "unconnected-(J17-Pad3)") (class "Default")
      (node (ref "J17") (pin "3") (pinfunction "3_3") (pintype "passive"))
    )
    (net (code "246") (name "unconnected-(J17-Pad5)") (class "Default")
      (node (ref "J17") (pin "5") (pinfunction "5_5") (pintype "passive"))
    )
    (net (code "247") (name "unconnected-(J17-Pad6)") (class "Default")
      (node (ref "J17") (pin "6") (pinfunction "6_6") (pintype "passive"))
    )
    (net (code "248") (name "unconnected-(J17-Pad7)") (class "Default")
      (node (ref "J17") (pin "7") (pinfunction "7_7") (pintype "passive"))
    )
    (net (code "249") (name "unconnected-(J18-Pad1)") (class "Default")
      (node (ref "J18") (pin "1") (pinfunction "1_1") (pintype "passive"))
    )
    (net (code "250") (name "unconnected-(J18-Pad2)") (class "Default")
      (node (ref "J18") (pin "2") (pinfunction "2_2") (pintype "passive"))
    )
    (net (code "251") (name "unconnected-(J18-Pad3)") (class "Default")
      (node (ref "J18") (pin "3") (pinfunction "3_3") (pintype "passive"))
    )
    (net (code "252") (name "unconnected-(J18-Pad6)") (class "Default")
      (node (ref "J18") (pin "6") (pinfunction "6_6") (pintype "passive"))
    )
    (net (code "253") (name "unconnected-(J18-Pad7)") (class "Default")
      (node (ref "J18") (pin "7") (pinfunction "7_7") (pintype "passive"))
    )
    (net (code "254") (name "unconnected-(J19-Pad1)") (class "Default")
      (node (ref "J19") (pin "1") (pinfunction "1_1") (pintype "passive"))
    )
    (net (code "255") (name "unconnected-(J19-Pad3)") (class "Default")
      (node (ref "J19") (pin "3") (pinfunction "3_3") (pintype "passive"))
    )
    (net (code "256") (name "unconnected-(J19-Pad5)") (class "Default")
      (node (ref "J19") (pin "5") (pinfunction "5_5") (pintype "passive"))
    )
    (net (code "257") (name "unconnected-(J19-Pad6)") (class "Default")
      (node (ref "J19") (pin "6") (pinfunction "6_6") (pintype "passive"))
    )
    (net (code "258") (name "unconnected-(J20-Pad1)") (class "Default")
      (node (ref "J20") (pin "1") (pinfunction "1_1") (pintype "passive"))
    )
    (net (code "259") (name "unconnected-(J20-Pad2)") (class "Default")
      (node (ref "J20") (pin "2") (pinfunction "2_2") (pintype "passive"))
    )
    (net (code "260") (name "unconnected-(J20-Pad3)") (class "Default")
      (node (ref "J20") (pin "3") (pinfunction "3_3") (pintype "passive"))
    )
    (net (code "261") (name "unconnected-(J20-Pad4)") (class "Default")
      (node (ref "J20") (pin "4") (pinfunction "4_4") (pintype "passive"))
    )
    (net (code "262") (name "unconnected-(J20-Pad5)") (class "Default")
      (node (ref "J20") (pin "5") (pinfunction "5_5") (pintype "passive"))
    )
    (net (code "263") (name "unconnected-(J20-Pad6)") (class "Default")
      (node (ref "J20") (pin "6") (pinfunction "6_6") (pintype "passive"))
    )
    (net (code "264") (name "unconnected-(J21-Pad3)") (class "Default")
      (node (ref "J21") (pin "3") (pinfunction "3_3") (pintype "passive"))
    )
    (net (code "265") (name "unconnected-(J21-Pad4)") (class "Default")
      (node (ref "J21") (pin "4") (pinfunction "4_4") (pintype "passive"))
    )
    (net (code "266") (name "unconnected-(J21-Pad5)") (class "Default")
      (node (ref "J21") (pin "5") (pinfunction "5_5") (pintype "passive"))
    )
    (net (code "267") (name "unconnected-(J21-Pad6)") (class "Default")
      (node (ref "J21") (pin "6") (pinfunction "6_6") (pintype "passive"))
    )
    (net (code "268") (name "unconnected-(J21-Pad7)") (class "Default")
      (node (ref "J21") (pin "7") (pinfunction "7_7") (pintype "passive"))
    )
    (net (code "269") (name "unconnected-(J22-Pad3)") (class "Default")
      (node (ref "J22") (pin "3") (pinfunction "3_3") (pintype "passive"))
    )
    (net (code "270") (name "unconnected-(J22-Pad5)") (class "Default")
      (node (ref "J22") (pin "5") (pinfunction "5_5") (pintype "passive"))
    )
    (net (code "271") (name "unconnected-(J22-Pad7)") (class "Default")
      (node (ref "J22") (pin "7") (pinfunction "7_7") (pintype "passive"))
    )
  )
)
